# Talon_SDI12.net
KiCad netlist of a schematic drawn in EAGLE
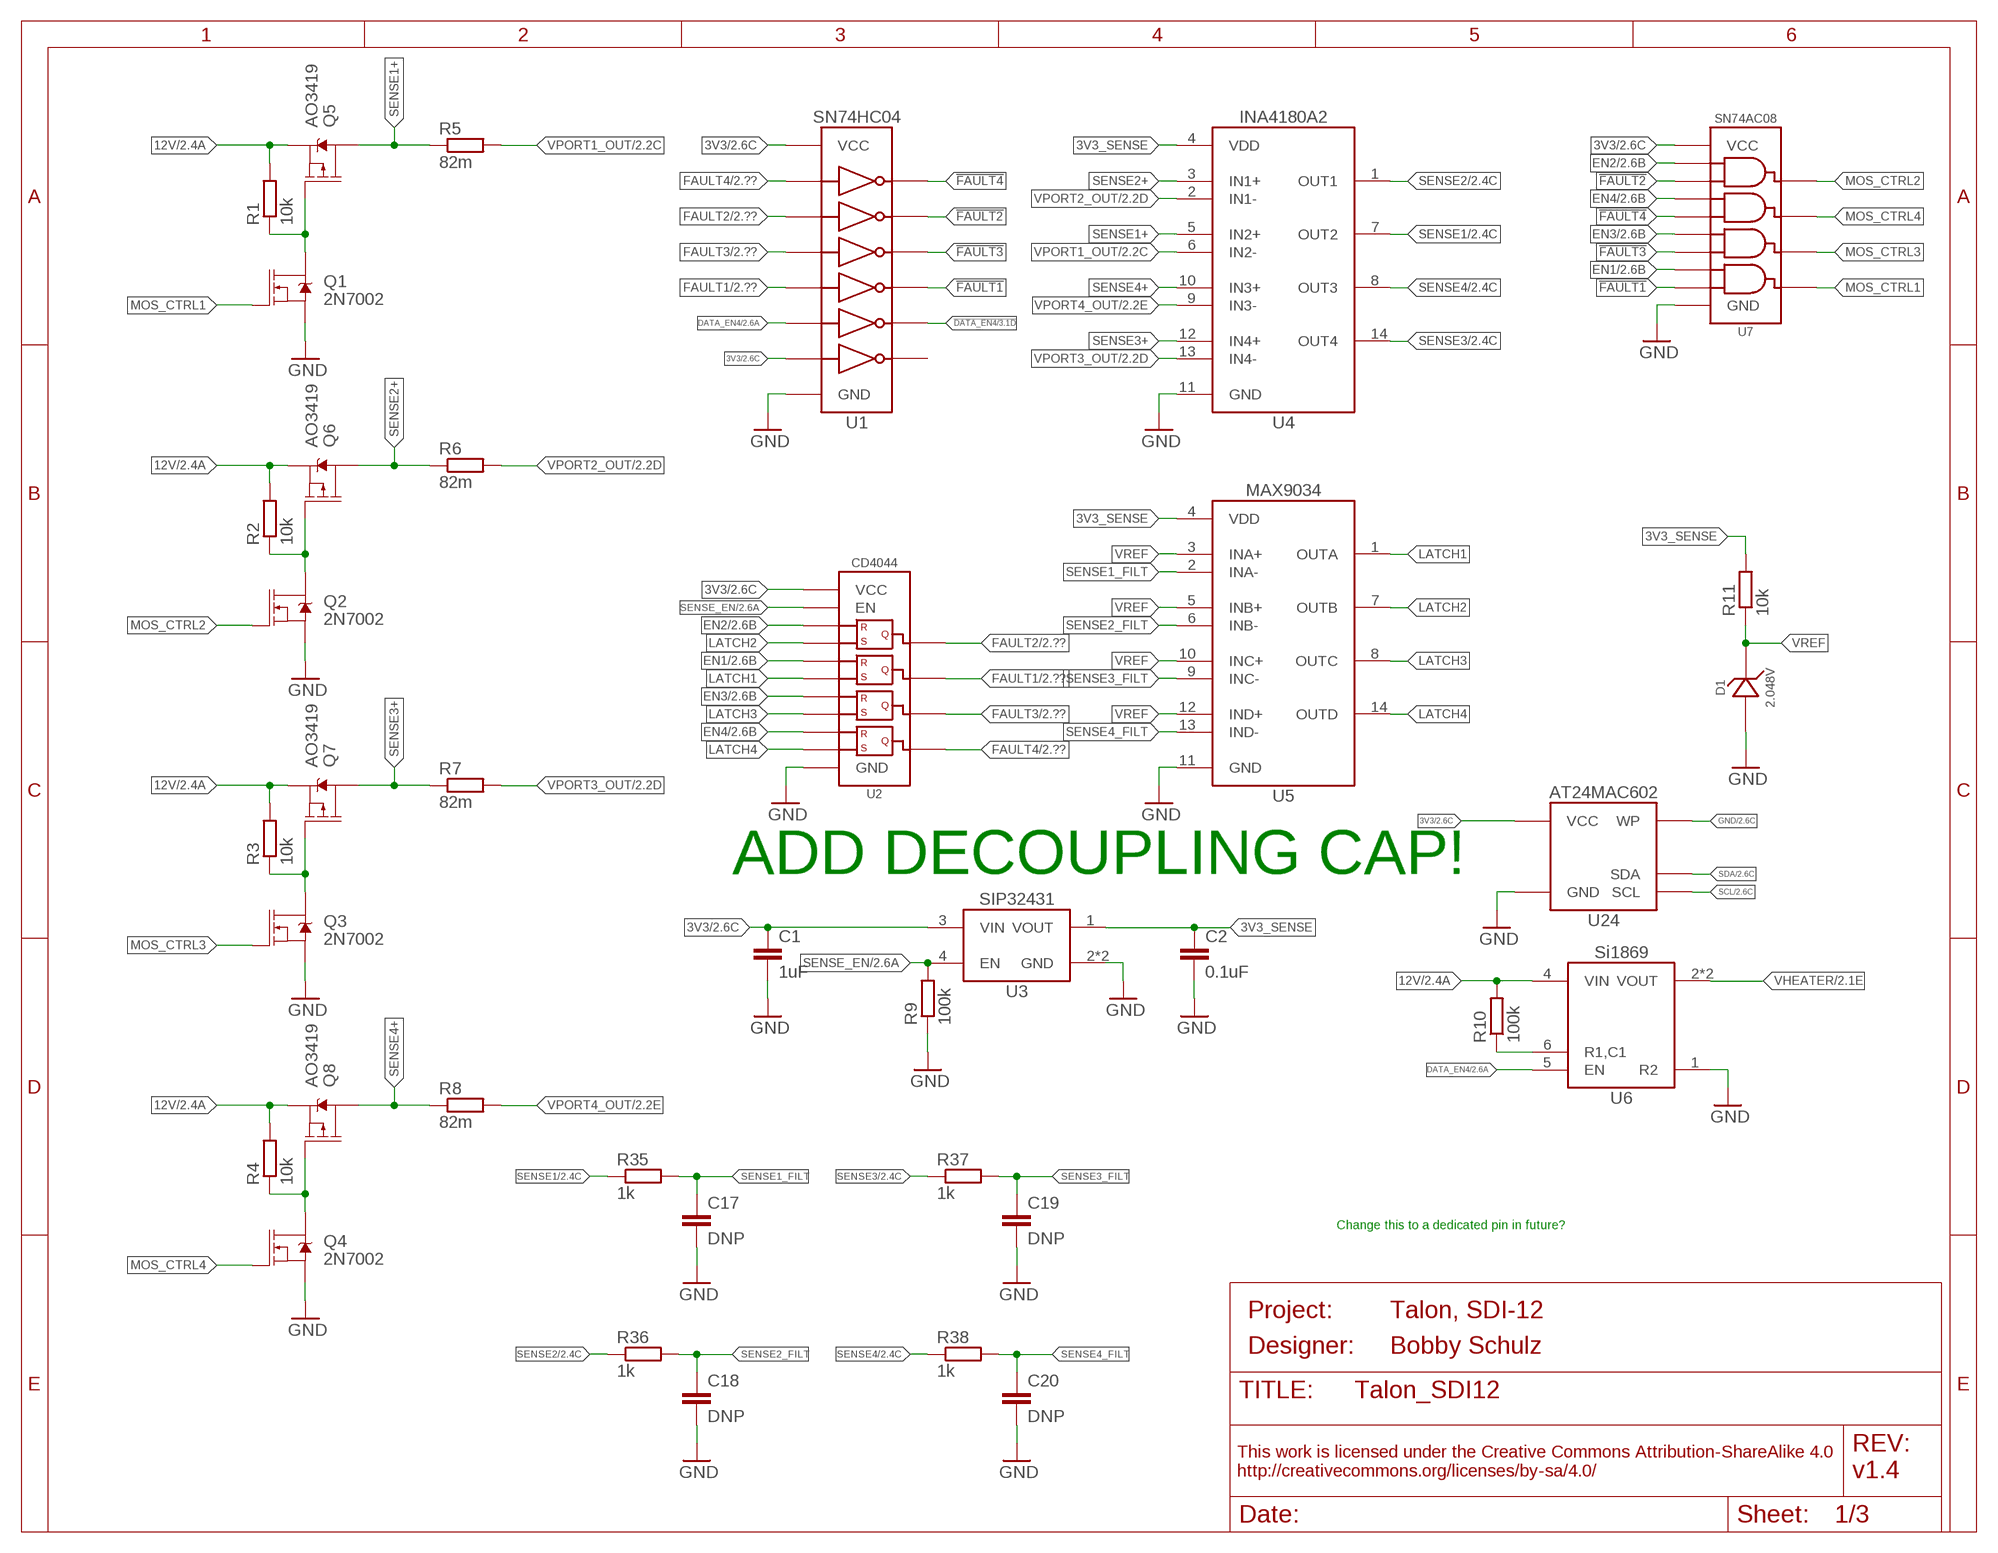
[diagram p0: schematic, sheet 1]
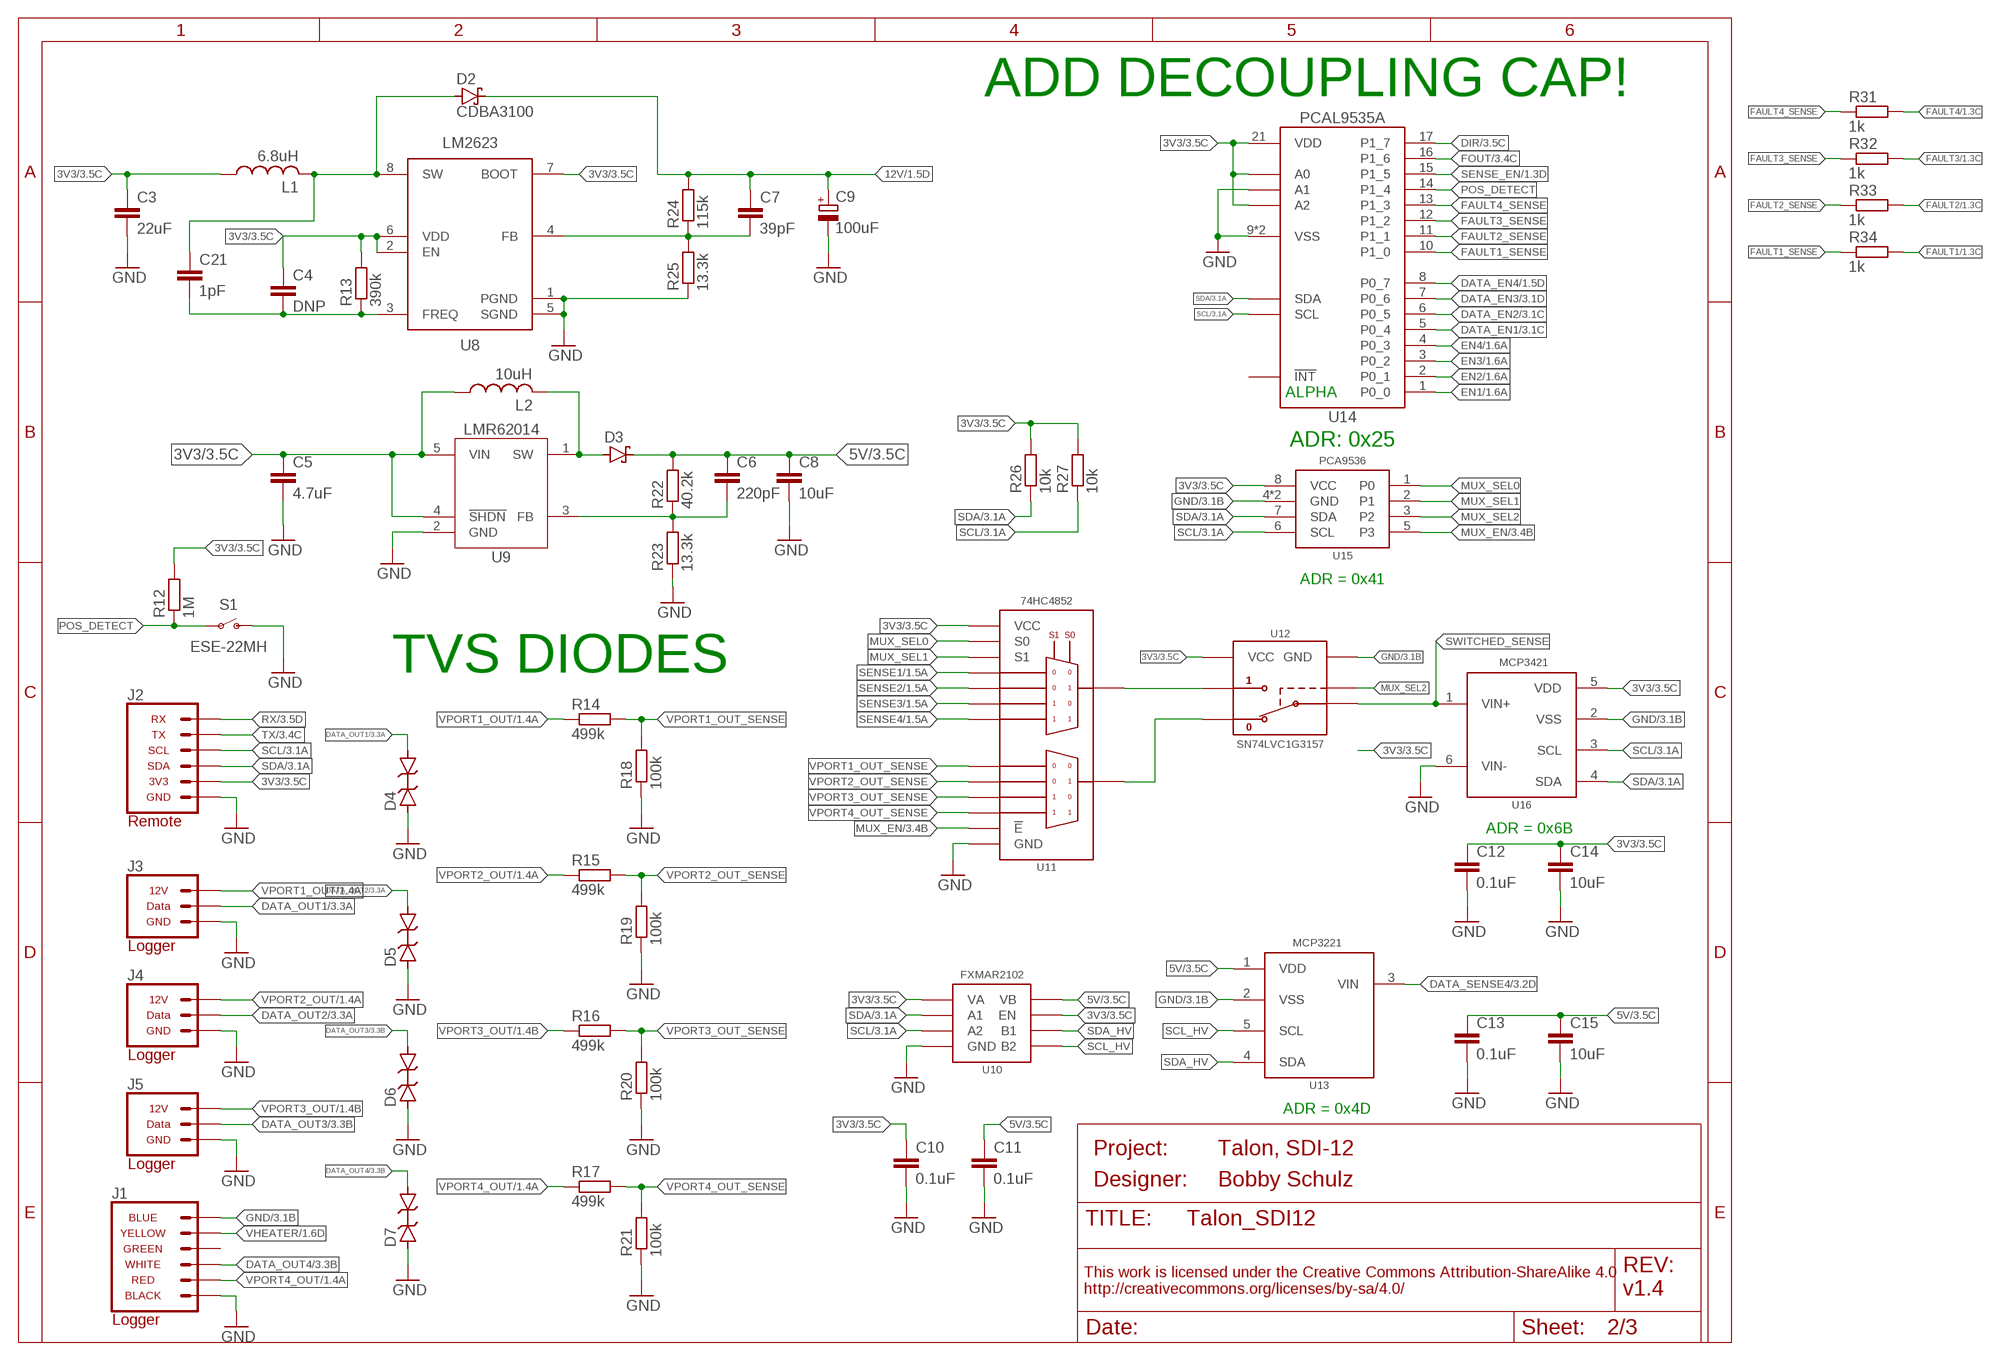
[diagram p1: schematic, sheet 2]
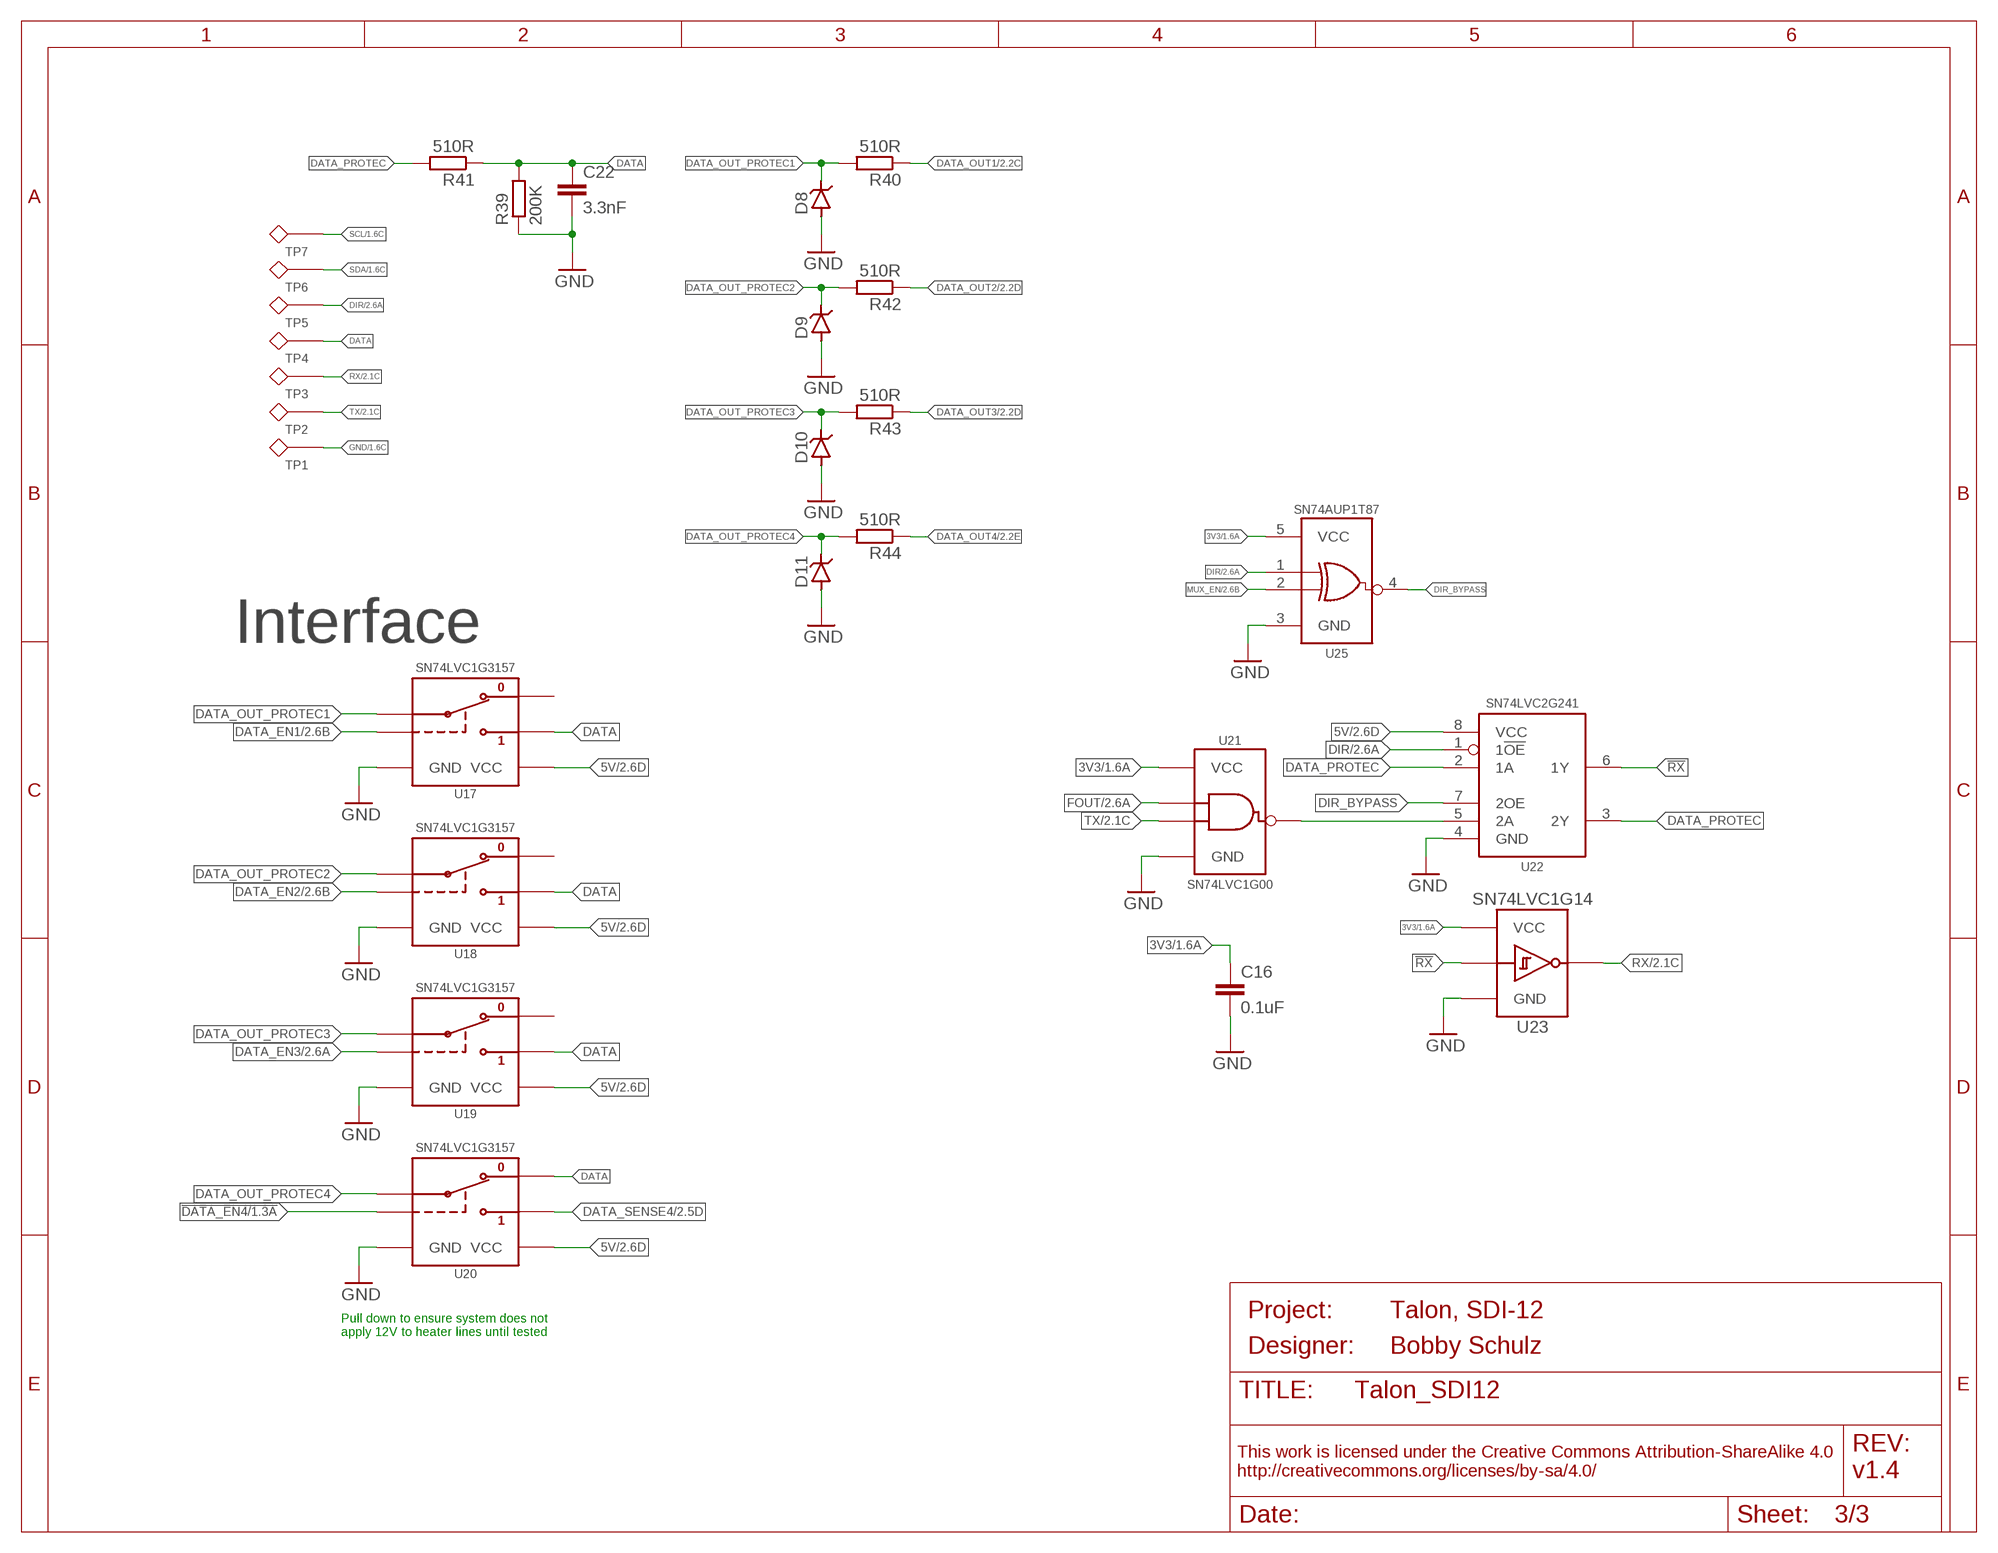
[diagram p2: schematic, sheet 3]

(export (version "E")
  (design (tool "Eeschema 10.0.6"))
  (components
    (comp (ref "C3")
      (value "22uF")
      (footprint "eagle-import:C0805")
      (fields (field (name "MF") "Murata") (field (name "MPN") "GRM219R61C226ME15L"))
      (libsource (lib "eagle-import") (part "C-EUC080522UF"))
    )
    (comp (ref "C4")
      (value "DNP")
      (footprint "eagle-import:C0402")
      (fields
        (field (name "MF") "Murata")
        (field (name "MPN") "GCM155R71C104KA55D")
        (field (name "DIGIKEY") "DNP")
        (field (name "MF_1") "N/A")
        (field (name "MPN_1") "DNP")
      )
      (libsource (lib "eagle-import") (part "C-EUC04020.1UF"))
    )
    (comp (ref "C5")
      (value "4.7uF")
      (footprint "eagle-import:C0805")
      (fields (field (name "MF") "Kemet") (field (name "MPN") "C0805C475K4RACTU"))
      (libsource (lib "eagle-import") (part "C-EUC08054.7UF"))
    )
    (comp (ref "C6")
      (value "220pF")
      (footprint "eagle-import:C0603")
      (fields (field (name "MF") "Kemet") (field (name "MPN") "C0603C221J5GACTU"))
      (libsource (lib "eagle-import") (part "C-EUC0603220PF"))
    )
    (comp (ref "C7")
      (value "39pF")
      (footprint "eagle-import:C0402")
      (fields (field (name "MF") "Kemet") (field (name "MPN") "C0402C390J5GAC7867"))
      (libsource (lib "eagle-import") (part "C-EUC040239PF"))
    )
    (comp (ref "C8")
      (value "10uF")
      (footprint "eagle-import:C0805")
      (fields
        (field (name "MF") "Murata")
        (field (name "MPN") "GRM21BR61C106KE15K")
        (field (name "DIGIKEY") "587-2985-1-ND")
        (field (name "MF_1") "Taiyo Yuden")
        (field (name "MPN_1") "TMK212BBJ106KG-T")
      )
      (libsource (lib "eagle-import") (part "C-EUC080510UF"))
    )
    (comp (ref "C9")
      (value "100uF")
      (footprint "eagle-import:C2917")
      (fields (field (name "MF") "Vishay") (field (name "MPN") "293D107X0016D2TE3"))
      (libsource (lib "eagle-import") (part "CTANT_EU2917"))
    )
    (comp (ref "C10")
      (value "0.1uF")
      (footprint "eagle-import:C0402")
      (fields (field (name "MF") "Murata") (field (name "MPN") "GCM155R71C104KA55D"))
      (libsource (lib "eagle-import") (part "C-EUC04020.1UF"))
    )
    (comp (ref "C11")
      (value "0.1uF")
      (footprint "eagle-import:C0402")
      (fields (field (name "MF") "Murata") (field (name "MPN") "GCM155R71C104KA55D"))
      (libsource (lib "eagle-import") (part "C-EUC04020.1UF"))
    )
    (comp (ref "C12")
      (value "0.1uF")
      (footprint "eagle-import:C0402")
      (fields (field (name "MF") "Murata") (field (name "MPN") "GCM155R71C104KA55D"))
      (libsource (lib "eagle-import") (part "C-EUC04020.1UF"))
    )
    (comp (ref "C13")
      (value "0.1uF")
      (footprint "eagle-import:C0402")
      (fields (field (name "MF") "Murata") (field (name "MPN") "GCM155R71C104KA55D"))
      (libsource (lib "eagle-import") (part "C-EUC04020.1UF"))
    )
    (comp (ref "C14")
      (value "10uF")
      (footprint "eagle-import:C0805")
      (fields (field (name "MF") "Murata") (field (name "MPN") "GRM21BR61C106KE15K"))
      (libsource (lib "eagle-import") (part "C-EUC080510UF"))
    )
    (comp (ref "C15")
      (value "10uF")
      (footprint "eagle-import:C0805")
      (fields (field (name "MF") "Murata") (field (name "MPN") "GRM21BR61C106KE15K"))
      (libsource (lib "eagle-import") (part "C-EUC080510UF"))
    )
    (comp (ref "C21")
      (value "1pF")
      (footprint "eagle-import:C0402")
      (fields (field (name "MF") "Murata") (field (name "MPN") "GJM1555C1H1R0BB01D"))
      (libsource (lib "eagle-import") (part "C-EUC04021PF"))
    )
    (comp (ref "D2")
      (value "CDBA3100")
      (footprint "eagle-import:DO214AC")
      (fields (field (name "MF") "Comchip") (field (name "MPN") "CDBA3100-HF"))
      (libsource (lib "eagle-import") (part "DIODE_SCHOTTKYDO-214AC"))
    )
    (comp (ref "D3")
      (value "DIODE_SCHOTTKYSOD-123")
      (footprint "eagle-import:SOD-123")
      (fields (field (name "MF") "ON Semiconductor") (field (name "MPN") "MBR0520LT1G"))
      (libsource (lib "eagle-import") (part "DIODE_SCHOTTKYSOD-123"))
    )
    (comp (ref "D4")
      (value "12V")
      (footprint "eagle-import:D0402")
      (fields
        (field (name "MF") "Diodes Inc")
        (field (name "MPN") "D5V0L1B2LP4-7B")
        (field (name "DIGIKEY") "D12V0L1B2LP-7BDICT-ND")
        (field (name "MPN_1") "D12V0L1B2LP-7B")
      )
      (libsource (lib "eagle-import") (part "DIODE_ESD_BI_0402_D5V0L1"))
    )
    (comp (ref "D5")
      (value "12V")
      (footprint "eagle-import:D0402")
      (fields
        (field (name "MF") "Diodes Inc")
        (field (name "MPN") "D5V0L1B2LP4-7B")
        (field (name "DIGIKEY") "D12V0L1B2LP-7BDICT-ND")
        (field (name "MPN_1") "D12V0L1B2LP-7B")
      )
      (libsource (lib "eagle-import") (part "DIODE_ESD_BI_0402_D5V0L1"))
    )
    (comp (ref "D6")
      (value "12V")
      (footprint "eagle-import:D0402")
      (fields
        (field (name "MF") "Diodes Inc")
        (field (name "MPN") "D5V0L1B2LP4-7B")
        (field (name "DIGIKEY") "D12V0L1B2LP-7BDICT-ND")
        (field (name "MPN_1") "D12V0L1B2LP-7B")
      )
      (libsource (lib "eagle-import") (part "DIODE_ESD_BI_0402_D5V0L1"))
    )
    (comp (ref "D7")
      (value "12V")
      (footprint "eagle-import:D0402")
      (fields
        (field (name "MF") "Diodes Inc")
        (field (name "MPN") "D5V0L1B2LP4-7B")
        (field (name "DIGIKEY") "D12V0L1B2LP-7BDICT-ND")
        (field (name "MPN_1") "D12V0L1B2LP-7B")
      )
      (libsource (lib "eagle-import") (part "DIODE_ESD_BI_0402_D5V0L1"))
    )
    (comp (ref "J1")
      (value "CONN_APOGEE_LOGGER")
      (footprint "eagle-import:1X06_M8_PHOENIX_1456022_BOARDLOCK")
      (fields
        (field (name "DISP") "Logger")
        (field (name "MF") "Phoenix Contact")
        (field (name "MPN") "1456022")
      )
      (libsource (lib "eagle-import") (part "CONN_APOGEE_LOGGER"))
    )
    (comp (ref "J2")
      (value "CONN_TALON_REMOTE")
      (footprint "eagle-import:1X06_MICROLOCKPLUS")
      (fields (field (name "DISP") "Remote") (field (name "MF") "Molex") (field (name "MPN") "2059570671"))
      (libsource (lib "eagle-import") (part "CONN_TALON_REMOTE"))
    )
    (comp (ref "J3")
      (value "CONN_SDI-12_LOGGERM8_TE_BOARDLOCK")
      (footprint "eagle-import:1X03_M8_TE_T40410_BOARDLOCK")
      (fields
        (field (name "DISP") "Logger")
        (field (name "MF") "TE Connectivity")
        (field (name "MPN") "T4041037031-000")
      )
      (libsource (lib "eagle-import") (part "CONN_SDI-12_LOGGERM8_TE_BOARDLOCK"))
    )
    (comp (ref "J4")
      (value "CONN_SDI-12_LOGGERM8_TE_BOARDLOCK")
      (footprint "eagle-import:1X03_M8_TE_T40410_BOARDLOCK")
      (fields
        (field (name "DISP") "Logger")
        (field (name "MF") "TE Connectivity")
        (field (name "MPN") "T4041037031-000")
      )
      (libsource (lib "eagle-import") (part "CONN_SDI-12_LOGGERM8_TE_BOARDLOCK"))
    )
    (comp (ref "J5")
      (value "CONN_SDI-12_LOGGERM8_TE_BOARDLOCK")
      (footprint "eagle-import:1X03_M8_TE_T40410_BOARDLOCK")
      (fields
        (field (name "DISP") "Logger")
        (field (name "MF") "TE Connectivity")
        (field (name "MPN") "T4041037031-000")
      )
      (libsource (lib "eagle-import") (part "CONN_SDI-12_LOGGERM8_TE_BOARDLOCK"))
    )
    (comp (ref "L1")
      (value "6.8uH")
      (footprint "eagle-import:WE-MAIA(4.1X4.1)")
      (fields (field (name "MF") "Wurth") (field (name "MPN") "78438357068"))
      (libsource (lib "eagle-import") (part "INDUCTOR_MAIA_4.1X4.1"))
    )
    (comp (ref "L2")
      (value "10uH")
      (footprint "eagle-import:1008")
      (fields (field (name "MF") "Wurth") (field (name "MPN") "74438323100"))
      (libsource (lib "eagle-import") (part "INDUCTOR_1008"))
    )
    (comp (ref "R12")
      (value "1M")
      (footprint "eagle-import:R0402")
      (fields (field (name "MF") "Yageo") (field (name "MPN") "RC0402FR-071ML"))
      (libsource (lib "eagle-import") (part "R-EU_R04021M"))
    )
    (comp (ref "R13")
      (value "390k")
      (footprint "eagle-import:R0603")
      (fields (field (name "MF") "Yageo") (field (name "MPN") "RC0603FR-07390KL"))
      (libsource (lib "eagle-import") (part "R-EU_R0603390K"))
    )
    (comp (ref "R14")
      (value "499k")
      (footprint "eagle-import:R0603")
      (fields (field (name "MF") "Yageo") (field (name "MPN") "RC0603FR-07499KL"))
      (libsource (lib "eagle-import") (part "R-EU_R0603499K"))
    )
    (comp (ref "R15")
      (value "499k")
      (footprint "eagle-import:R0603")
      (fields (field (name "MF") "Yageo") (field (name "MPN") "RC0603FR-07499KL"))
      (libsource (lib "eagle-import") (part "R-EU_R0603499K"))
    )
    (comp (ref "R16")
      (value "499k")
      (footprint "eagle-import:R0603")
      (fields (field (name "MF") "Yageo") (field (name "MPN") "RC0603FR-07499KL"))
      (libsource (lib "eagle-import") (part "R-EU_R0603499K"))
    )
    (comp (ref "R17")
      (value "499k")
      (footprint "eagle-import:R0603")
      (fields (field (name "MF") "Yageo") (field (name "MPN") "RC0603FR-07499KL"))
      (libsource (lib "eagle-import") (part "R-EU_R0603499K"))
    )
    (comp (ref "R18")
      (value "100k")
      (footprint "eagle-import:R0402")
      (fields (field (name "MF") "Yageo") (field (name "MPN") "RC0402FR-07100KL"))
      (libsource (lib "eagle-import") (part "R-EU_R0402100K"))
    )
    (comp (ref "R19")
      (value "100k")
      (footprint "eagle-import:R0402")
      (fields (field (name "MF") "Yageo") (field (name "MPN") "RC0402FR-07100KL"))
      (libsource (lib "eagle-import") (part "R-EU_R0402100K"))
    )
    (comp (ref "R20")
      (value "100k")
      (footprint "eagle-import:R0402")
      (fields (field (name "MF") "Yageo") (field (name "MPN") "RC0402FR-07100KL"))
      (libsource (lib "eagle-import") (part "R-EU_R0402100K"))
    )
    (comp (ref "R21")
      (value "100k")
      (footprint "eagle-import:R0402")
      (fields (field (name "MF") "Yageo") (field (name "MPN") "RC0402FR-07100KL"))
      (libsource (lib "eagle-import") (part "R-EU_R0402100K"))
    )
    (comp (ref "R22")
      (value "40.2k")
      (footprint "eagle-import:R0603")
      (fields (field (name "MF") "Stackpole") (field (name "MPN") "RMCF0603FT40K2"))
      (libsource (lib "eagle-import") (part "R-EU_R060340.2K"))
    )
    (comp (ref "R23")
      (value "13.3k")
      (footprint "eagle-import:R0603")
      (fields (field (name "MF") "Yageo") (field (name "MPN") "RC0603FR-0713K3L"))
      (libsource (lib "eagle-import") (part "R-EU_R060313.3K"))
    )
    (comp (ref "R24")
      (value "115k")
      (footprint "eagle-import:R0603")
      (fields (field (name "MF") "Yageo") (field (name "MPN") "RC0603FR-07115KL"))
      (libsource (lib "eagle-import") (part "R-EU_R0603115K"))
    )
    (comp (ref "R25")
      (value "13.3k")
      (footprint "eagle-import:R0603")
      (fields (field (name "MF") "Yageo") (field (name "MPN") "RC0603FR-0713K3L"))
      (libsource (lib "eagle-import") (part "R-EU_R060313.3K"))
    )
    (comp (ref "R26")
      (value "10k")
      (footprint "eagle-import:R0402")
      (fields (field (name "MF") "Yageo") (field (name "MPN") "RC0402FR-0710KL"))
      (libsource (lib "eagle-import") (part "R-EU_R040210K"))
    )
    (comp (ref "R27")
      (value "10k")
      (footprint "eagle-import:R0402")
      (fields (field (name "MF") "Yageo") (field (name "MPN") "RC0402FR-0710KL"))
      (libsource (lib "eagle-import") (part "R-EU_R040210K"))
    )
    (comp (ref "R31")
      (value "1k")
      (footprint "eagle-import:R0402")
      (fields (field (name "MF") "Yageo") (field (name "MPN") "RC0402FR-071KL"))
      (libsource (lib "eagle-import") (part "R-EU_R04021K"))
    )
    (comp (ref "R32")
      (value "1k")
      (footprint "eagle-import:R0402")
      (fields (field (name "MF") "Yageo") (field (name "MPN") "RC0402FR-071KL"))
      (libsource (lib "eagle-import") (part "R-EU_R04021K"))
    )
    (comp (ref "R33")
      (value "1k")
      (footprint "eagle-import:R0402")
      (fields (field (name "MF") "Yageo") (field (name "MPN") "RC0402FR-071KL"))
      (libsource (lib "eagle-import") (part "R-EU_R04021K"))
    )
    (comp (ref "R34")
      (value "1k")
      (footprint "eagle-import:R0402")
      (fields (field (name "MF") "Yageo") (field (name "MPN") "RC0402FR-071KL"))
      (libsource (lib "eagle-import") (part "R-EU_R04021K"))
    )
    (comp (ref "S1")
      (value "ESE-22MH")
      (footprint "eagle-import:ESE-22MH")
      (fields (field (name "MF") "Panasonic") (field (name "MPN") "ESE-22MH24"))
      (libsource (lib "eagle-import") (part "SPSTESE-22MH"))
    )
    (comp (ref "U8")
      (value "LM2621")
      (footprint "eagle-import:DGK_S-PDSO-G8")
      (fields
        (field (name "DISP") "LM2621")
        (field (name "MF") "TI")
        (field (name "MPN") "LM2621MMX/NOPB")
        (field (name "DIGIKEY") "LM2623AMM/NOPBCT-ND")
        (field (name "DISP_1") "LM2623")
        (field (name "MPN_1") "LM2623AMM/NOPB")
      )
      (libsource (lib "eagle-import") (part "LM2621"))
    )
    (comp (ref "U9")
      (value "LMR62014SOT23")
      (footprint "eagle-import:DBV0005A")
      (fields
        (field (name "DISP") "LMR62014")
        (field (name "MF") "TI")
        (field (name "MPN") "LMR62014XMF/NOPB")
      )
      (libsource (lib "eagle-import") (part "LMR62014SOT23"))
    )
    (comp (ref "U10")
      (value "FXMAR2102UMLP")
      (footprint "eagle-import:UQFN-8_1.4X1.2")
      (fields
        (field (name "DISP") "FXMAR2102")
        (field (name "MF") "OnSemi")
        (field (name "MPN") "FXMAR2102UMX-F106")
      )
      (libsource (lib "eagle-import") (part "FXMAR2102UMLP"))
    )
    (comp (ref "U11")
      (value "74HC4852")
      (footprint "eagle-import:VQFN-16")
      (fields
        (field (name "DISP") "74HC4852")
        (field (name "MF") "Nexperia")
        (field (name "MPN") "74HC4852BQ-Q100,11")
      )
      (libsource (lib "eagle-import") (part "74HC4852"))
    )
    (comp (ref "U12")
      (value "SN74LVC1G3157SC70")
      (footprint "eagle-import:DCK_R-PDSO-G6")
      (fields
        (field (name "DISP") "SN74LVC1G3157")
        (field (name "MF") "TI")
        (field (name "MPN") "SN74LVC1G3157DCKR")
      )
      (libsource (lib "eagle-import") (part "SN74LVC1G3157SC70"))
    )
    (comp (ref "U13")
      (value "MCP3221")
      (footprint "eagle-import:SOT23-5")
      (fields (field (name "DISP") "MCP3221") (field (name "MF") "TI") (field (name "MPN") "MCP3221A5T-I/OT"))
      (libsource (lib "eagle-import") (part "MCP3221"))
    )
    (comp (ref "U14")
      (value "PCAL9535AQFN")
      (footprint "eagle-import:QFN24")
      (fields
        (field (name "DISP") "PCAL9535A")
        (field (name "MF") "NXP")
        (field (name "MPN") "PCAL9535AHF,128")
      )
      (libsource (lib "eagle-import") (part "PCAL955AQFN3"))
    )
    (comp (ref "U15")
      (value "PCA9536DFN")
      (footprint "eagle-import:DFN_8_3X3")
      (fields (field (name "MF") "NXP") (field (name "MPN") "PCA9536TK,118"))
      (libsource (lib "eagle-import") (part "PCA9536DFN"))
    )
    (comp (ref "U16")
      (value "MCP3421A3")
      (footprint "eagle-import:SOT23-6L")
      (fields
        (field (name "DISP") "MCP3421")
        (field (name "MF") "Microchip")
        (field (name "MPN") "MCP3421A3T-E/CH")
      )
      (libsource (lib "eagle-import") (part "MCP3421A3"))
    )
    (comp (ref "C1")
      (value "1uF")
      (footprint "eagle-import:C0603")
      (fields (field (name "MF") "Yaiyo Yuden") (field (name "MPN") "TMK107B7105KA-T"))
      (libsource (lib "eagle-import") (part "C-EUC06031UF"))
    )
    (comp (ref "C2")
      (value "0.1uF")
      (footprint "eagle-import:C0402")
      (fields (field (name "MF") "Murata") (field (name "MPN") "GCM155R71C104KA55D"))
      (libsource (lib "eagle-import") (part "C-EUC04020.1UF"))
    )
    (comp (ref "C17")
      (value "DNP")
      (footprint "eagle-import:C0402")
      (fields
        (field (name "MF") "Murata")
        (field (name "MPN") "GCM155R71C104KA55D")
        (field (name "DIGIKEY") "DNP")
        (field (name "MF_1") "N/A")
        (field (name "MPN_1") "DNP")
      )
      (libsource (lib "eagle-import") (part "C-EUC04020.1UF"))
    )
    (comp (ref "C18")
      (value "DNP")
      (footprint "eagle-import:C0402")
      (fields
        (field (name "MF") "Murata")
        (field (name "MPN") "GCM155R71C104KA55D")
        (field (name "DIGIKEY") "DNP")
        (field (name "MF_1") "N/A")
        (field (name "MPN_1") "DNP")
      )
      (libsource (lib "eagle-import") (part "C-EUC04020.1UF"))
    )
    (comp (ref "C19")
      (value "DNP")
      (footprint "eagle-import:C0402")
      (fields
        (field (name "MF") "Murata")
        (field (name "MPN") "GCM155R71C104KA55D")
        (field (name "DIGIKEY") "DNP")
        (field (name "MF_1") "N/A")
        (field (name "MPN_1") "DNP")
      )
      (libsource (lib "eagle-import") (part "C-EUC04020.1UF"))
    )
    (comp (ref "C20")
      (value "DNP")
      (footprint "eagle-import:C0402")
      (fields
        (field (name "MF") "Murata")
        (field (name "MPN") "GCM155R71C104KA55D")
        (field (name "DIGIKEY") "DNP")
        (field (name "MF_1") "N/A")
        (field (name "MPN_1") "DNP")
      )
      (libsource (lib "eagle-import") (part "C-EUC04020.1UF"))
    )
    (comp (ref "D1")
      (value "2.048V")
      (footprint "eagle-import:SOT23-3")
      (fields (field (name "MF") "TI") (field (name "MPN") "LM4040CIM3-2.0/NOPB"))
      (libsource (lib "eagle-import") (part "LM40402.048"))
    )
    (comp (ref "Q1")
      (value "2N7002")
      (footprint "eagle-import:SOT23-3")
      (fields (field (name "MF") "Nexperia") (field (name "MPN") "2N7002P,215"))
      (libsource (lib "eagle-import") (part "MOSFET-NCH-2N7002P"))
    )
    (comp (ref "Q2")
      (value "2N7002")
      (footprint "eagle-import:SOT23-3")
      (fields (field (name "MF") "Nexperia") (field (name "MPN") "2N7002P,215"))
      (libsource (lib "eagle-import") (part "MOSFET-NCH-2N7002P"))
    )
    (comp (ref "Q3")
      (value "2N7002")
      (footprint "eagle-import:SOT23-3")
      (fields (field (name "MF") "Nexperia") (field (name "MPN") "2N7002P,215"))
      (libsource (lib "eagle-import") (part "MOSFET-NCH-2N7002P"))
    )
    (comp (ref "Q4")
      (value "2N7002")
      (footprint "eagle-import:SOT23-3")
      (fields (field (name "MF") "Nexperia") (field (name "MPN") "2N7002P,215"))
      (libsource (lib "eagle-import") (part "MOSFET-NCH-2N7002P"))
    )
    (comp (ref "Q5")
      (value "AO3419")
      (footprint "eagle-import:SOT23-3")
      (fields (field (name "MF") "Alpha and Omega"))
      (libsource (lib "eagle-import") (part "MOSFET-PCH-AO3419"))
    )
    (comp (ref "Q6")
      (value "AO3419")
      (footprint "eagle-import:SOT23-3")
      (fields (field (name "MF") "Alpha and Omega"))
      (libsource (lib "eagle-import") (part "MOSFET-PCH-AO3419"))
    )
    (comp (ref "Q7")
      (value "AO3419")
      (footprint "eagle-import:SOT23-3")
      (fields (field (name "MF") "Alpha and Omega"))
      (libsource (lib "eagle-import") (part "MOSFET-PCH-AO3419"))
    )
    (comp (ref "Q8")
      (value "AO3419")
      (footprint "eagle-import:SOT23-3")
      (fields (field (name "MF") "Alpha and Omega"))
      (libsource (lib "eagle-import") (part "MOSFET-PCH-AO3419"))
    )
    (comp (ref "R1")
      (value "10k")
      (footprint "eagle-import:R0402")
      (fields (field (name "MF") "Yageo") (field (name "MPN") "RC0402FR-0710KL"))
      (libsource (lib "eagle-import") (part "R-EU_R040210K"))
    )
    (comp (ref "R2")
      (value "10k")
      (footprint "eagle-import:R0402")
      (fields (field (name "MF") "Yageo") (field (name "MPN") "RC0402FR-0710KL"))
      (libsource (lib "eagle-import") (part "R-EU_R040210K"))
    )
    (comp (ref "R3")
      (value "10k")
      (footprint "eagle-import:R0402")
      (fields (field (name "MF") "Yageo") (field (name "MPN") "RC0402FR-0710KL"))
      (libsource (lib "eagle-import") (part "R-EU_R040210K"))
    )
    (comp (ref "R4")
      (value "10k")
      (footprint "eagle-import:R0402")
      (fields (field (name "MF") "Yageo") (field (name "MPN") "RC0402FR-0710KL"))
      (libsource (lib "eagle-import") (part "R-EU_R040210K"))
    )
    (comp (ref "R5")
      (value "82m")
      (footprint "eagle-import:R0603")
      (fields (field (name "MF") "Susumu") (field (name "MPN") "RL0816T-R082-F"))
      (libsource (lib "eagle-import") (part "R-EU_R06030.082"))
    )
    (comp (ref "R6")
      (value "82m")
      (footprint "eagle-import:R0603")
      (fields (field (name "MF") "Susumu") (field (name "MPN") "RL0816T-R082-F"))
      (libsource (lib "eagle-import") (part "R-EU_R06030.082"))
    )
    (comp (ref "R7")
      (value "82m")
      (footprint "eagle-import:R0603")
      (fields (field (name "MF") "Susumu") (field (name "MPN") "RL0816T-R082-F"))
      (libsource (lib "eagle-import") (part "R-EU_R06030.082"))
    )
    (comp (ref "R8")
      (value "82m")
      (footprint "eagle-import:R0603")
      (fields (field (name "MF") "Susumu") (field (name "MPN") "RL0816T-R082-F"))
      (libsource (lib "eagle-import") (part "R-EU_R06030.082"))
    )
    (comp (ref "R9")
      (value "100k")
      (footprint "eagle-import:R0402")
      (fields (field (name "MF") "Yageo") (field (name "MPN") "RC0402FR-07100KL"))
      (libsource (lib "eagle-import") (part "R-EU_R0402100K"))
    )
    (comp (ref "R10")
      (value "100k")
      (footprint "eagle-import:R0402")
      (fields (field (name "MF") "Yageo") (field (name "MPN") "RC0402FR-07100KL"))
      (libsource (lib "eagle-import") (part "R-EU_R0402100K"))
    )
    (comp (ref "R11")
      (value "10k")
      (footprint "eagle-import:R0402")
      (fields (field (name "MF") "Yageo") (field (name "MPN") "RC0402FR-0710KL"))
      (libsource (lib "eagle-import") (part "R-EU_R040210K"))
    )
    (comp (ref "R35")
      (value "1k")
      (footprint "eagle-import:R0402")
      (fields (field (name "MF") "Yageo") (field (name "MPN") "RC0402FR-071KL"))
      (libsource (lib "eagle-import") (part "R-EU_R04021K"))
    )
    (comp (ref "R36")
      (value "1k")
      (footprint "eagle-import:R0402")
      (fields (field (name "MF") "Yageo") (field (name "MPN") "RC0402FR-071KL"))
      (libsource (lib "eagle-import") (part "R-EU_R04021K"))
    )
    (comp (ref "R37")
      (value "1k")
      (footprint "eagle-import:R0402")
      (fields (field (name "MF") "Yageo") (field (name "MPN") "RC0402FR-071KL"))
      (libsource (lib "eagle-import") (part "R-EU_R04021K"))
    )
    (comp (ref "R38")
      (value "1k")
      (footprint "eagle-import:R0402")
      (fields (field (name "MF") "Yageo") (field (name "MPN") "RC0402FR-071KL"))
      (libsource (lib "eagle-import") (part "R-EU_R04021K"))
    )
    (comp (ref "U1")
      (value "SN74HC04")
      (footprint "eagle-import:TSSOP14")
      (fields (field (name "MF") "TI") (field (name "MPN") "SN74HC04PWR"))
      (libsource (lib "eagle-import") (part "SN74HC04"))
    )
    (comp (ref "U2")
      (value "CD4044")
      (footprint "eagle-import:TSSOP16")
      (fields (field (name "DISP") "CD4044") (field (name "MF") "TI") (field (name "MPN") "CD4044BPWR"))
      (libsource (lib "eagle-import") (part "CD4044"))
    )
    (comp (ref "U3")
      (value "SIP32431TDFN")
      (footprint "eagle-import:TDFN_4")
      (fields
        (field (name "DISP") "SIP32431")
        (field (name "MF") "Vishay")
        (field (name "MPN") "SIP32431DNP3-T1GE4")
      )
      (libsource (lib "eagle-import") (part "SIP3243TDFN1"))
    )
    (comp (ref "U4")
      (value "INA4180A2")
      (footprint "eagle-import:TSSOP14")
      (fields (field (name "DISP") "INA4180A2") (field (name "MF") "TI") (field (name "MPN") "INA4180A2IPWR"))
      (libsource (lib "eagle-import") (part "INA4180A2"))
    )
    (comp (ref "U5")
      (value "MAX9034TSSOP")
      (footprint "eagle-import:TSSOP14")
      (fields (field (name "DISP") "MAX9034") (field (name "MF") "Maxim") (field (name "MPN") "MAX9034AUD+T"))
      (libsource (lib "eagle-import") (part "MAX9034TSSOP"))
    )
    (comp (ref "U6")
      (value "SI1869")
      (footprint "eagle-import:SC-70_6")
      (fields
        (field (name "DISP") "Si1869")
        (field (name "MF") "Vishay")
        (field (name "MPN") "SI1869DH-T1-E3")
      )
      (libsource (lib "eagle-import") (part "SI1869"))
    )
    (comp (ref "U7")
      (value "SN74AC08")
      (footprint "eagle-import:TSSOP14")
      (fields (field (name "MF") "TI") (field (name "MPN") "SN74AC08PWR"))
      (libsource (lib "eagle-import") (part "SN74AC08"))
    )
    (comp (ref "U24")
      (value "AT24MAC602SOT23")
      (footprint "eagle-import:SOT23-5")
      (fields
        (field (name "DISP") "AT24MAC602")
        (field (name "MF") "Microchip")
        (field (name "MPN") "AT24MAC602-STUM-T")
      )
      (libsource (lib "eagle-import") (part "AT24MAC02SOT236"))
    )
    (comp (ref "C16")
      (value "0.1uF")
      (footprint "eagle-import:C0402")
      (fields (field (name "MF") "Murata") (field (name "MPN") "GCM155R71C104KA55D"))
      (libsource (lib "eagle-import") (part "C-EUC04020.1UF"))
    )
    (comp (ref "C22")
      (value "3.3nF")
      (footprint "eagle-import:C0402")
      (fields (field (name "MF") "Yageo") (field (name "MPN") "CC0402KRX7R9BB332"))
      (libsource (lib "eagle-import") (part "C-EUC04023.3NF"))
    )
    (comp (ref "D8")
      (value "DIODE_ZENERSOD-323")
      (footprint "eagle-import:SOD323-R")
      (fields (field (name "MF") "Vishay") (field (name "MPN") "BZX384B5V1-HE3-08"))
      (libsource (lib "eagle-import") (part "DIODE_ZENERSOD-323"))
    )
    (comp (ref "D9")
      (value "DIODE_ZENERSOD-323")
      (footprint "eagle-import:SOD323-R")
      (fields (field (name "MF") "Vishay") (field (name "MPN") "BZX384B5V1-HE3-08"))
      (libsource (lib "eagle-import") (part "DIODE_ZENERSOD-323"))
    )
    (comp (ref "D10")
      (value "DIODE_ZENERSOD-323")
      (footprint "eagle-import:SOD323-R")
      (fields (field (name "MF") "Vishay") (field (name "MPN") "BZX384B5V1-HE3-08"))
      (libsource (lib "eagle-import") (part "DIODE_ZENERSOD-323"))
    )
    (comp (ref "D11")
      (value "DIODE_ZENERSOD-323")
      (footprint "eagle-import:SOD323-R")
      (fields (field (name "MF") "Vishay") (field (name "MPN") "BZX384B5V1-HE3-08"))
      (libsource (lib "eagle-import") (part "DIODE_ZENERSOD-323"))
    )
    (comp (ref "R39")
      (value "200K")
      (footprint "eagle-import:R0402")
      (fields
        (field (name "MF") "Yageo")
        (field (name "MPN") "RC0402FR-07200KL")
        (field (name "VALUE_PART") "200k")
      )
      (libsource (lib "eagle-import") (part "R-EU_R0402200K"))
    )
    (comp (ref "R40")
      (value "510R")
      (footprint "eagle-import:R0402")
      (fields
        (field (name "MF") "Yageo")
        (field (name "MPN") "RC0402FR-07510RL")
        (field (name "VALUE_PART") "510")
      )
      (libsource (lib "eagle-import") (part "R-EU_R0402510"))
    )
    (comp (ref "R41")
      (value "510R")
      (footprint "eagle-import:R0402")
      (fields
        (field (name "MF") "Yageo")
        (field (name "MPN") "RC0402FR-07510RL")
        (field (name "VALUE_PART") "510")
      )
      (libsource (lib "eagle-import") (part "R-EU_R0402510"))
    )
    (comp (ref "R42")
      (value "510R")
      (footprint "eagle-import:R0402")
      (fields
        (field (name "MF") "Yageo")
        (field (name "MPN") "RC0402FR-07510RL")
        (field (name "VALUE_PART") "510")
      )
      (libsource (lib "eagle-import") (part "R-EU_R0402510"))
    )
    (comp (ref "R43")
      (value "510R")
      (footprint "eagle-import:R0402")
      (fields
        (field (name "MF") "Yageo")
        (field (name "MPN") "RC0402FR-07510RL")
        (field (name "VALUE_PART") "510")
      )
      (libsource (lib "eagle-import") (part "R-EU_R0402510"))
    )
    (comp (ref "R44")
      (value "510R")
      (footprint "eagle-import:R0402")
      (fields
        (field (name "MF") "Yageo")
        (field (name "MPN") "RC0402FR-07510RL")
        (field (name "VALUE_PART") "510")
      )
      (libsource (lib "eagle-import") (part "R-EU_R0402510"))
    )
    (comp (ref "TP1")
      (value "TESTPOINTRCU")
      (footprint "eagle-import:TESTPOINT_0603")
      (fields (field (name "MF") "TE Connectivity") (field (name "MPN") "RCU-0C"))
      (libsource (lib "eagle-import") (part "TESTPOINTRCU"))
    )
    (comp (ref "TP2")
      (value "TESTPOINTRCU")
      (footprint "eagle-import:TESTPOINT_0603")
      (fields (field (name "MF") "TE Connectivity") (field (name "MPN") "RCU-0C"))
      (libsource (lib "eagle-import") (part "TESTPOINTRCU"))
    )
    (comp (ref "TP3")
      (value "TESTPOINTRCU")
      (footprint "eagle-import:TESTPOINT_0603")
      (fields (field (name "MF") "TE Connectivity") (field (name "MPN") "RCU-0C"))
      (libsource (lib "eagle-import") (part "TESTPOINTRCU"))
    )
    (comp (ref "TP4")
      (value "TESTPOINTRCU")
      (footprint "eagle-import:TESTPOINT_0603")
      (fields (field (name "MF") "TE Connectivity") (field (name "MPN") "RCU-0C"))
      (libsource (lib "eagle-import") (part "TESTPOINTRCU"))
    )
    (comp (ref "TP5")
      (value "TESTPOINTRCU")
      (footprint "eagle-import:TESTPOINT_0603")
      (fields (field (name "MF") "TE Connectivity") (field (name "MPN") "RCU-0C"))
      (libsource (lib "eagle-import") (part "TESTPOINTRCU"))
    )
    (comp (ref "TP6")
      (value "TESTPOINTRCU")
      (footprint "eagle-import:TESTPOINT_0603")
      (fields (field (name "MF") "TE Connectivity") (field (name "MPN") "RCU-0C"))
      (libsource (lib "eagle-import") (part "TESTPOINTRCU"))
    )
    (comp (ref "TP7")
      (value "TESTPOINTRCU")
      (footprint "eagle-import:TESTPOINT_0603")
      (fields (field (name "MF") "TE Connectivity") (field (name "MPN") "RCU-0C"))
      (libsource (lib "eagle-import") (part "TESTPOINTRCU"))
    )
    (comp (ref "U17")
      (value "SN74LVC1G3157SC70")
      (footprint "eagle-import:DCK_R-PDSO-G6")
      (fields
        (field (name "DISP") "SN74LVC1G3157")
        (field (name "MF") "TI")
        (field (name "MPN") "SN74LVC1G3157DCKR")
      )
      (libsource (lib "eagle-import") (part "SN74LVC1G3157SC70"))
    )
    (comp (ref "U18")
      (value "SN74LVC1G3157SC70")
      (footprint "eagle-import:DCK_R-PDSO-G6")
      (fields
        (field (name "DISP") "SN74LVC1G3157")
        (field (name "MF") "TI")
        (field (name "MPN") "SN74LVC1G3157DCKR")
      )
      (libsource (lib "eagle-import") (part "SN74LVC1G3157SC70"))
    )
    (comp (ref "U19")
      (value "SN74LVC1G3157SC70")
      (footprint "eagle-import:DCK_R-PDSO-G6")
      (fields
        (field (name "DISP") "SN74LVC1G3157")
        (field (name "MF") "TI")
        (field (name "MPN") "SN74LVC1G3157DCKR")
      )
      (libsource (lib "eagle-import") (part "SN74LVC1G3157SC70"))
    )
    (comp (ref "U20")
      (value "SN74LVC1G3157SC70")
      (footprint "eagle-import:DCK_R-PDSO-G6")
      (fields
        (field (name "DISP") "SN74LVC1G3157")
        (field (name "MF") "TI")
        (field (name "MPN") "SN74LVC1G3157DCKR")
      )
      (libsource (lib "eagle-import") (part "SN74LVC1G3157SC70"))
    )
    (comp (ref "U21")
      (value "SN74LVC1G00SC70")
      (footprint "eagle-import:DCK_R-PDSO-G5")
      (fields (field (name "DISP") "SN74LVC1G00") (field (name "MPN") "SN74LVC1G00DCKR"))
      (libsource (lib "eagle-import") (part "SN74LVC1G00SC70"))
    )
    (comp (ref "U22")
      (value "SN74LVC2G241DCU")
      (footprint "eagle-import:DCU_(R-PDSO-G8)")
      (fields (field (name "MF") "TI") (field (name "MPN") "SN74LVC2G241DCUT"))
      (libsource (lib "eagle-import") (part "SN74LVC2G241DCU"))
    )
    (comp (ref "U23")
      (value "SN74LVC1G14DCK")
      (footprint "eagle-import:DCK_R-PDSO-G5")
      (fields
        (field (name "DISP") "SN74LVC1G14")
        (field (name "MF") "TI")
        (field (name "MPN") "SN74LVC1G14DCKR")
      )
      (libsource (lib "eagle-import") (part "SN741G14DCKLVC"))
    )
    (comp (ref "U25")
      (value "SN74AUP1T87")
      (footprint "eagle-import:DCK_R-PDSO-G5")
      (fields
        (field (name "DISP") "SN74AUP1T87")
        (field (name "MF") "TI")
        (field (name "MPN") "SN74AUP1T87DCKR")
      )
      (libsource (lib "eagle-import") (part "SN74AUP1T87"))
    )
  )
  (nets
    (net (code "1") (name "3V3") (class "Default")
      (node (ref "C1") (pin "1") (pinfunction "1_1") (pintype "passive"))
      (node (ref "C10") (pin "1") (pinfunction "1_1") (pintype "passive"))
      (node (ref "C12") (pin "1") (pinfunction "1_1") (pintype "passive"))
      (node (ref "C14") (pin "1") (pinfunction "1_1") (pintype "passive"))
      (node (ref "C16") (pin "1") (pinfunction "1_1") (pintype "passive"))
      (node (ref "C3") (pin "1") (pinfunction "1_1") (pintype "passive"))
      (node (ref "C4") (pin "1") (pinfunction "1_1") (pintype "passive"))
      (node (ref "C5") (pin "1") (pinfunction "1_1") (pintype "passive"))
      (node (ref "J2") (pin "2") (pinfunction "3V3_2") (pintype "passive"))
      (node (ref "L1") (pin "P$1") (pinfunction "1_P$1") (pintype "passive"))
      (node (ref "L2") (pin "1") (pinfunction "1_1") (pintype "passive"))
      (node (ref "R12") (pin "2") (pinfunction "2_2") (pintype "passive"))
      (node (ref "R13") (pin "2") (pinfunction "2_2") (pintype "passive"))
      (node (ref "R26") (pin "2") (pinfunction "2_2") (pintype "passive"))
      (node (ref "R27") (pin "2") (pinfunction "2_2") (pintype "passive"))
      (node (ref "U1") (pin "13") (pinfunction "A6_13") (pintype "input"))
      (node (ref "U1") (pin "14") (pinfunction "VCC_14") (pintype "power_in"))
      (node (ref "U10") (pin "1") (pinfunction "VA_1") (pintype "power_in"))
      (node (ref "U10") (pin "5") (pinfunction "EN_5") (pintype "input"))
      (node (ref "U11") (pin "16") (pinfunction "VCC_16") (pintype "power_in"))
      (node (ref "U12") (pin "5") (pinfunction "VCC_5") (pintype "power_in"))
      (node (ref "U14") (pin "18") (pinfunction "A0_18") (pintype "input"))
      (node (ref "U14") (pin "21") (pinfunction "VDD_21") (pintype "power_in"))
      (node (ref "U14") (pin "24") (pinfunction "A2_24") (pintype "input"))
      (node (ref "U15") (pin "8") (pinfunction "VCC_8") (pintype "power_in"))
      (node (ref "U16") (pin "5") (pinfunction "VDD_5") (pintype "passive"))
      (node (ref "U2") (pin "16") (pinfunction "VCC_16") (pintype "power_in"))
      (node (ref "U21") (pin "5") (pinfunction "VCC_5") (pintype "power_in"))
      (node (ref "U23") (pin "5") (pinfunction "VCC_5") (pintype "power_in"))
      (node (ref "U24") (pin "4") (pinfunction "VCC_4") (pintype "power_in"))
      (node (ref "U25") (pin "5") (pinfunction "VCC_5") (pintype "power_in"))
      (node (ref "U3") (pin "3") (pinfunction "VIN_3") (pintype "power_in"))
      (node (ref "U7") (pin "14") (pinfunction "VCC_14") (pintype "power_in"))
      (node (ref "U8") (pin "2") (pinfunction "EN_2") (pintype "bidirectional"))
      (node (ref "U8") (pin "6") (pinfunction "VDD_6") (pintype "bidirectional"))
      (node (ref "U8") (pin "7") (pinfunction "BOOT_7") (pintype "bidirectional"))
      (node (ref "U9") (pin "4") (pinfunction "~{SHDN}_4") (pintype "input"))
      (node (ref "U9") (pin "5") (pinfunction "VIN_5") (pintype "power_in"))
    )
    (net (code "2") (name "3V3_SENSE") (class "Default")
      (node (ref "C2") (pin "1") (pinfunction "1_1") (pintype "passive"))
      (node (ref "R11") (pin "2") (pinfunction "2_2") (pintype "passive"))
      (node (ref "U3") (pin "1") (pinfunction "VOUT_1") (pintype "power_in"))
      (node (ref "U4") (pin "4") (pinfunction "VDD_4") (pintype "power_in"))
      (node (ref "U5") (pin "4") (pinfunction "VDD_4") (pintype "power_in"))
    )
    (net (code "3") (name "5V") (class "Default")
      (node (ref "C11") (pin "1") (pinfunction "1_1") (pintype "passive"))
      (node (ref "C13") (pin "1") (pinfunction "1_1") (pintype "passive"))
      (node (ref "C15") (pin "1") (pinfunction "1_1") (pintype "passive"))
      (node (ref "C6") (pin "1") (pinfunction "1_1") (pintype "passive"))
      (node (ref "C8") (pin "1") (pinfunction "1_1") (pintype "passive"))
      (node (ref "D3") (pin "CAT") (pinfunction "C_CAT") (pintype "passive"))
      (node (ref "R22") (pin "2") (pinfunction "2_2") (pintype "passive"))
      (node (ref "U10") (pin "8") (pinfunction "VB_8") (pintype "power_in"))
      (node (ref "U13") (pin "1") (pinfunction "VDD_1") (pintype "power_in"))
      (node (ref "U17") (pin "5") (pinfunction "VCC_5") (pintype "power_in"))
      (node (ref "U18") (pin "5") (pinfunction "VCC_5") (pintype "power_in"))
      (node (ref "U19") (pin "5") (pinfunction "VCC_5") (pintype "power_in"))
      (node (ref "U20") (pin "5") (pinfunction "VCC_5") (pintype "power_in"))
      (node (ref "U22") (pin "8") (pinfunction "VCC_8") (pintype "power_in"))
    )
    (net (code "4") (name "12V") (class "Default")
      (node (ref "C7") (pin "1") (pinfunction "1_1") (pintype "passive"))
      (node (ref "C9") (pin "+") (pinfunction "+_+") (pintype "passive"))
      (node (ref "D2") (pin "C") (pinfunction "C_C") (pintype "passive"))
      (node (ref "Q5") (pin "2") (pinfunction "S_2") (pintype "bidirectional"))
      (node (ref "Q6") (pin "2") (pinfunction "S_2") (pintype "bidirectional"))
      (node (ref "Q7") (pin "2") (pinfunction "S_2") (pintype "bidirectional"))
      (node (ref "Q8") (pin "2") (pinfunction "S_2") (pintype "bidirectional"))
      (node (ref "R1") (pin "2") (pinfunction "2_2") (pintype "passive"))
      (node (ref "R10") (pin "2") (pinfunction "2_2") (pintype "passive"))
      (node (ref "R2") (pin "2") (pinfunction "2_2") (pintype "passive"))
      (node (ref "R24") (pin "2") (pinfunction "2_2") (pintype "passive"))
      (node (ref "R3") (pin "2") (pinfunction "2_2") (pintype "passive"))
      (node (ref "R4") (pin "2") (pinfunction "2_2") (pintype "passive"))
      (node (ref "U6") (pin "4") (pinfunction "VIN_4") (pintype "bidirectional"))
    )
    (net (code "5") (name "DATA") (class "Default")
      (node (ref "C22") (pin "1") (pinfunction "1_1") (pintype "passive"))
      (node (ref "R39") (pin "2") (pinfunction "2_2") (pintype "passive"))
      (node (ref "R41") (pin "1") (pinfunction "1_1") (pintype "passive"))
      (node (ref "TP4") (pin "1") (pinfunction "P$1_1") (pintype "bidirectional"))
      (node (ref "U17") (pin "1") (pinfunction "B2_1") (pintype "bidirectional"))
      (node (ref "U18") (pin "1") (pinfunction "B2_1") (pintype "bidirectional"))
      (node (ref "U19") (pin "1") (pinfunction "B2_1") (pintype "bidirectional"))
      (node (ref "U20") (pin "3") (pinfunction "B1_3") (pintype "bidirectional"))
    )
    (net (code "6") (name "DATA_EN1") (class "Default")
      (node (ref "U14") (pin "5") (pinfunction "P0_4_5") (pintype "bidirectional"))
      (node (ref "U17") (pin "6") (pinfunction "S_6") (pintype "input"))
    )
    (net (code "7") (name "DATA_EN2") (class "Default")
      (node (ref "U14") (pin "6") (pinfunction "P0_5_6") (pintype "bidirectional"))
      (node (ref "U18") (pin "6") (pinfunction "S_6") (pintype "input"))
    )
    (net (code "8") (name "DATA_EN3") (class "Default")
      (node (ref "U14") (pin "7") (pinfunction "P0_6_7") (pintype "bidirectional"))
      (node (ref "U19") (pin "6") (pinfunction "S_6") (pintype "input"))
    )
    (net (code "9") (name "DATA_EN4") (class "Default")
      (node (ref "U1") (pin "11") (pinfunction "A5_11") (pintype "input"))
      (node (ref "U14") (pin "8") (pinfunction "P0_7_8") (pintype "bidirectional"))
      (node (ref "U6") (pin "5") (pinfunction "EN_5") (pintype "bidirectional"))
    )
    (net (code "10") (name "DATA_OUT1") (class "Default")
      (node (ref "D4") (pin "2") (pinfunction "C_2") (pintype "passive"))
      (node (ref "J3") (pin "4") (pinfunction "DATA_4") (pintype "passive"))
      (node (ref "R40") (pin "1") (pinfunction "1_1") (pintype "passive"))
    )
    (net (code "11") (name "DATA_OUT2") (class "Default")
      (node (ref "D5") (pin "2") (pinfunction "C_2") (pintype "passive"))
      (node (ref "J4") (pin "4") (pinfunction "DATA_4") (pintype "passive"))
      (node (ref "R42") (pin "1") (pinfunction "1_1") (pintype "passive"))
    )
    (net (code "12") (name "DATA_OUT3") (class "Default")
      (node (ref "D6") (pin "2") (pinfunction "C_2") (pintype "passive"))
      (node (ref "J5") (pin "4") (pinfunction "DATA_4") (pintype "passive"))
      (node (ref "R43") (pin "1") (pinfunction "1_1") (pintype "passive"))
    )
    (net (code "13") (name "DATA_OUT4") (class "Default")
      (node (ref "D7") (pin "2") (pinfunction "C_2") (pintype "passive"))
      (node (ref "J1") (pin "3") (pinfunction "3_3") (pintype "passive"))
      (node (ref "R44") (pin "1") (pinfunction "1_1") (pintype "passive"))
    )
    (net (code "14") (name "DATA_OUT_PROTEC1") (class "Default")
      (node (ref "D8") (pin "C") (pinfunction "C_C") (pintype "passive"))
      (node (ref "R40") (pin "2") (pinfunction "2_2") (pintype "passive"))
      (node (ref "U17") (pin "4") (pinfunction "A_4") (pintype "bidirectional"))
    )
    (net (code "15") (name "DATA_OUT_PROTEC2") (class "Default")
      (node (ref "D9") (pin "C") (pinfunction "C_C") (pintype "passive"))
      (node (ref "R42") (pin "2") (pinfunction "2_2") (pintype "passive"))
      (node (ref "U18") (pin "4") (pinfunction "A_4") (pintype "bidirectional"))
    )
    (net (code "16") (name "DATA_OUT_PROTEC3") (class "Default")
      (node (ref "D10") (pin "C") (pinfunction "C_C") (pintype "passive"))
      (node (ref "R43") (pin "2") (pinfunction "2_2") (pintype "passive"))
      (node (ref "U19") (pin "4") (pinfunction "A_4") (pintype "bidirectional"))
    )
    (net (code "17") (name "DATA_OUT_PROTEC4") (class "Default")
      (node (ref "D11") (pin "C") (pinfunction "C_C") (pintype "passive"))
      (node (ref "R44") (pin "2") (pinfunction "2_2") (pintype "passive"))
      (node (ref "U20") (pin "4") (pinfunction "A_4") (pintype "bidirectional"))
    )
    (net (code "18") (name "DATA_PROTEC") (class "Default")
      (node (ref "R41") (pin "2") (pinfunction "2_2") (pintype "passive"))
      (node (ref "U22") (pin "2") (pinfunction "1A_2") (pintype "input"))
      (node (ref "U22") (pin "3") (pinfunction "2Y_3") (pintype "output"))
    )
    (net (code "19") (name "DATA_SENSE4") (class "Default")
      (node (ref "U13") (pin "3") (pinfunction "VIN_3") (pintype "input"))
      (node (ref "U20") (pin "1") (pinfunction "B2_1") (pintype "bidirectional"))
    )
    (net (code "20") (name "DIR") (class "Default")
      (node (ref "TP5") (pin "1") (pinfunction "P$1_1") (pintype "bidirectional"))
      (node (ref "U14") (pin "17") (pinfunction "P1_7_17") (pintype "bidirectional"))
      (node (ref "U22") (pin "1") (pinfunction "1~{OE}_1") (pintype "input"))
      (node (ref "U25") (pin "1") (pinfunction "A_1") (pintype "input"))
    )
    (net (code "21") (name "DIR_BYPASS") (class "Default")
      (node (ref "U22") (pin "7") (pinfunction "2OE_7") (pintype "input"))
      (node (ref "U25") (pin "4") (pinfunction "Y_4") (pintype "output"))
    )
    (net (code "22") (name "EN1") (class "Default")
      (node (ref "U14") (pin "1") (pinfunction "P0_0_1") (pintype "bidirectional"))
      (node (ref "U2") (pin "6") (pinfunction "R2_6") (pintype "input"))
      (node (ref "U7") (pin "12") (pinfunction "A4_12") (pintype "input"))
    )
    (net (code "23") (name "EN2") (class "Default")
      (node (ref "U14") (pin "2") (pinfunction "P0_1_2") (pintype "bidirectional"))
      (node (ref "U2") (pin "4") (pinfunction "R1_4") (pintype "input"))
      (node (ref "U7") (pin "1") (pinfunction "A1_1") (pintype "input"))
    )
    (net (code "24") (name "EN3") (class "Default")
      (node (ref "U14") (pin "3") (pinfunction "P0_2_3") (pintype "bidirectional"))
      (node (ref "U2") (pin "12") (pinfunction "R3_12") (pintype "input"))
      (node (ref "U7") (pin "9") (pinfunction "A3_9") (pintype "input"))
    )
    (net (code "25") (name "EN4") (class "Default")
      (node (ref "U14") (pin "4") (pinfunction "P0_3_4") (pintype "bidirectional"))
      (node (ref "U2") (pin "14") (pinfunction "R4_14") (pintype "input"))
      (node (ref "U7") (pin "4") (pinfunction "A2_4") (pintype "input"))
    )
    (net (code "26") (name "FAULT1") (class "Default")
      (node (ref "R34") (pin "2") (pinfunction "2_2") (pintype "passive"))
      (node (ref "U1") (pin "9") (pinfunction "A4_9") (pintype "input"))
      (node (ref "U2") (pin "9") (pinfunction "Q2_9") (pintype "output"))
    )
    (net (code "27") (name "FAULT1_SENSE") (class "Default")
      (node (ref "R34") (pin "1") (pinfunction "1_1") (pintype "passive"))
      (node (ref "U14") (pin "10") (pinfunction "P1_0_10") (pintype "bidirectional"))
    )
    (net (code "28") (name "FAULT2") (class "Default")
      (node (ref "R33") (pin "2") (pinfunction "2_2") (pintype "passive"))
      (node (ref "U1") (pin "3") (pinfunction "A2_3") (pintype "input"))
      (node (ref "U2") (pin "13") (pinfunction "Q1_13") (pintype "output"))
    )
    (net (code "29") (name "FAULT2_SENSE") (class "Default")
      (node (ref "R33") (pin "1") (pinfunction "1_1") (pintype "passive"))
      (node (ref "U14") (pin "11") (pinfunction "P1_1_11") (pintype "bidirectional"))
    )
    (net (code "30") (name "FAULT3") (class "Default")
      (node (ref "R32") (pin "2") (pinfunction "2_2") (pintype "passive"))
      (node (ref "U1") (pin "5") (pinfunction "A3_5") (pintype "input"))
      (node (ref "U2") (pin "10") (pinfunction "Q3_10") (pintype "output"))
    )
    (net (code "31") (name "FAULT3_SENSE") (class "Default")
      (node (ref "R32") (pin "1") (pinfunction "1_1") (pintype "passive"))
      (node (ref "U14") (pin "12") (pinfunction "P1_2_12") (pintype "bidirectional"))
    )
    (net (code "32") (name "FAULT4") (class "Default")
      (node (ref "R31") (pin "2") (pinfunction "2_2") (pintype "passive"))
      (node (ref "U1") (pin "1") (pinfunction "A1_1") (pintype "input"))
      (node (ref "U2") (pin "1") (pinfunction "Q4_1") (pintype "output"))
    )
    (net (code "33") (name "FAULT4_SENSE") (class "Default")
      (node (ref "R31") (pin "1") (pinfunction "1_1") (pintype "passive"))
      (node (ref "U14") (pin "13") (pinfunction "P1_3_13") (pintype "bidirectional"))
    )
    (net (code "34") (name "FOUT") (class "Default")
      (node (ref "U14") (pin "16") (pinfunction "P1_6_16") (pintype "bidirectional"))
      (node (ref "U21") (pin "1") (pinfunction "A_1") (pintype "input"))
    )
    (net (code "35") (name "GND") (class "Default")
      (node (ref "C1") (pin "2") (pinfunction "2_2") (pintype "passive"))
      (node (ref "C10") (pin "2") (pinfunction "2_2") (pintype "passive"))
      (node (ref "C11") (pin "2") (pinfunction "2_2") (pintype "passive"))
      (node (ref "C12") (pin "2") (pinfunction "2_2") (pintype "passive"))
      (node (ref "C13") (pin "2") (pinfunction "2_2") (pintype "passive"))
      (node (ref "C14") (pin "2") (pinfunction "2_2") (pintype "passive"))
      (node (ref "C15") (pin "2") (pinfunction "2_2") (pintype "passive"))
      (node (ref "C16") (pin "2") (pinfunction "2_2") (pintype "passive"))
      (node (ref "C17") (pin "2") (pinfunction "2_2") (pintype "passive"))
      (node (ref "C18") (pin "2") (pinfunction "2_2") (pintype "passive"))
      (node (ref "C19") (pin "2") (pinfunction "2_2") (pintype "passive"))
      (node (ref "C2") (pin "2") (pinfunction "2_2") (pintype "passive"))
      (node (ref "C20") (pin "2") (pinfunction "2_2") (pintype "passive"))
      (node (ref "C22") (pin "2") (pinfunction "2_2") (pintype "passive"))
      (node (ref "C3") (pin "2") (pinfunction "2_2") (pintype "passive"))
      (node (ref "C5") (pin "2") (pinfunction "2_2") (pintype "passive"))
      (node (ref "C8") (pin "2") (pinfunction "2_2") (pintype "passive"))
      (node (ref "C9") (pin "-") (pinfunction "-_-") (pintype "passive"))
      (node (ref "D1") (pin "2") (pinfunction "A_2") (pintype "power_in"))
      (node (ref "D10") (pin "A") (pinfunction "A_A") (pintype "passive"))
      (node (ref "D11") (pin "A") (pinfunction "A_A") (pintype "passive"))
      (node (ref "D4") (pin "1") (pinfunction "A_1") (pintype "passive"))
      (node (ref "D5") (pin "1") (pinfunction "A_1") (pintype "passive"))
      (node (ref "D6") (pin "1") (pinfunction "A_1") (pintype "passive"))
      (node (ref "D7") (pin "1") (pinfunction "A_1") (pintype "passive"))
      (node (ref "D8") (pin "A") (pinfunction "A_A") (pintype "passive"))
      (node (ref "D9") (pin "A") (pinfunction "A_A") (pintype "passive"))
      (node (ref "J1") (pin "1") (pinfunction "1_1") (pintype "passive"))
      (node (ref "J1") (pin "6") (pinfunction "6_6") (pintype "passive"))
      (node (ref "J2") (pin "1") (pinfunction "GND_1") (pintype "passive"))
      (node (ref "J3") (pin "3") (pinfunction "GND_3") (pintype "passive"))
      (node (ref "J4") (pin "3") (pinfunction "GND_3") (pintype "passive"))
      (node (ref "J5") (pin "3") (pinfunction "GND_3") (pintype "passive"))
      (node (ref "Q1") (pin "2") (pinfunction "S_2") (pintype "bidirectional"))
      (node (ref "Q2") (pin "2") (pinfunction "S_2") (pintype "bidirectional"))
      (node (ref "Q3") (pin "2") (pinfunction "S_2") (pintype "bidirectional"))
      (node (ref "Q4") (pin "2") (pinfunction "S_2") (pintype "bidirectional"))
      (node (ref "R18") (pin "1") (pinfunction "1_1") (pintype "passive"))
      (node (ref "R19") (pin "1") (pinfunction "1_1") (pintype "passive"))
      (node (ref "R20") (pin "1") (pinfunction "1_1") (pintype "passive"))
      (node (ref "R21") (pin "1") (pinfunction "1_1") (pintype "passive"))
      (node (ref "R23") (pin "1") (pinfunction "1_1") (pintype "passive"))
      (node (ref "R25") (pin "1") (pinfunction "1_1") (pintype "passive"))
      (node (ref "R39") (pin "1") (pinfunction "1_1") (pintype "passive"))
      (node (ref "R9") (pin "1") (pinfunction "1_1") (pintype "passive"))
      (node (ref "S1") (pin "1") (pinfunction "O_1") (pintype "passive"))
      (node (ref "TP1") (pin "1") (pinfunction "P$1_1") (pintype "bidirectional"))
      (node (ref "U1") (pin "7") (pinfunction "GND_7") (pintype "power_in"))
      (node (ref "U10") (pin "4") (pinfunction "GND_4") (pintype "power_in"))
      (node (ref "U11") (pin "8") (pinfunction "GND_8") (pintype "power_in"))
      (node (ref "U11") (pin "EP") (pinfunction "GND_EP") (pintype "power_in"))
      (node (ref "U12") (pin "2") (pinfunction "GND_2") (pintype "power_in"))
      (node (ref "U13") (pin "2") (pinfunction "VSS_2") (pintype "power_in"))
      (node (ref "U14") (pin "23") (pinfunction "A1_23") (pintype "input"))
      (node (ref "U14") (pin "9") (pinfunction "VSS_9") (pintype "power_in"))
      (node (ref "U14") (pin "EP") (pinfunction "VSS_EP") (pintype "power_in"))
      (node (ref "U15") (pin "4") (pinfunction "GND_4") (pintype "power_in"))
      (node (ref "U15") (pin "EP") (pinfunction "GND_EP") (pintype "power_in"))
      (node (ref "U16") (pin "2") (pinfunction "VSS_2") (pintype "passive"))
      (node (ref "U16") (pin "6") (pinfunction "VIN-_6") (pintype "input"))
      (node (ref "U17") (pin "2") (pinfunction "GND_2") (pintype "power_in"))
      (node (ref "U18") (pin "2") (pinfunction "GND_2") (pintype "power_in"))
      (node (ref "U19") (pin "2") (pinfunction "GND_2") (pintype "power_in"))
      (node (ref "U2") (pin "8") (pinfunction "GND_8") (pintype "power_in"))
      (node (ref "U20") (pin "2") (pinfunction "GND_2") (pintype "power_in"))
      (node (ref "U21") (pin "3") (pinfunction "GND_3") (pintype "power_in"))
      (node (ref "U22") (pin "4") (pinfunction "GND_4") (pintype "power_in"))
      (node (ref "U23") (pin "3") (pinfunction "GND_3") (pintype "power_in"))
      (node (ref "U24") (pin "2") (pinfunction "GND_2") (pintype "power_in"))
      (node (ref "U24") (pin "5") (pinfunction "WP_5") (pintype "input"))
      (node (ref "U25") (pin "3") (pinfunction "GND_3") (pintype "power_in"))
      (node (ref "U3") (pin "2") (pinfunction "GND_2") (pintype "power_in"))
      (node (ref "U3") (pin "EP") (pinfunction "GND_EP") (pintype "power_in"))
      (node (ref "U4") (pin "11") (pinfunction "GND_11") (pintype "power_in"))
      (node (ref "U5") (pin "11") (pinfunction "GND_11") (pintype "power_in"))
      (node (ref "U6") (pin "1") (pinfunction "R2_1") (pintype "bidirectional"))
      (node (ref "U7") (pin "7") (pinfunction "GND_7") (pintype "power_in"))
      (node (ref "U8") (pin "1") (pinfunction "PGND_1") (pintype "bidirectional"))
      (node (ref "U8") (pin "5") (pinfunction "SGND_5") (pintype "bidirectional"))
      (node (ref "U9") (pin "2") (pinfunction "GND_2") (pintype "power_in"))
    )
    (net (code "36") (name "LATCH1") (class "Default")
      (node (ref "U2") (pin "7") (pinfunction "S2_7") (pintype "input"))
      (node (ref "U5") (pin "1") (pinfunction "OUTA_1") (pintype "output"))
    )
    (net (code "37") (name "LATCH2") (class "Default")
      (node (ref "U2") (pin "3") (pinfunction "S1_3") (pintype "input"))
      (node (ref "U5") (pin "7") (pinfunction "OUTB_7") (pintype "output"))
    )
    (net (code "38") (name "LATCH3") (class "Default")
      (node (ref "U2") (pin "11") (pinfunction "S3_11") (pintype "input"))
      (node (ref "U5") (pin "8") (pinfunction "OUTC_8") (pintype "output"))
    )
    (net (code "39") (name "LATCH4") (class "Default")
      (node (ref "U2") (pin "15") (pinfunction "S4_15") (pintype "input"))
      (node (ref "U5") (pin "14") (pinfunction "OUTD_14") (pintype "output"))
    )
    (net (code "40") (name "MOS_CTRL1") (class "Default")
      (node (ref "Q1") (pin "1") (pinfunction "G_1") (pintype "bidirectional"))
      (node (ref "U7") (pin "11") (pinfunction "Y4_11") (pintype "output"))
    )
    (net (code "41") (name "MOS_CTRL2") (class "Default")
      (node (ref "Q2") (pin "1") (pinfunction "G_1") (pintype "bidirectional"))
      (node (ref "U7") (pin "3") (pinfunction "Y1_3") (pintype "output"))
    )
    (net (code "42") (name "MOS_CTRL3") (class "Default")
      (node (ref "Q3") (pin "1") (pinfunction "G_1") (pintype "bidirectional"))
      (node (ref "U7") (pin "8") (pinfunction "Y3_8") (pintype "output"))
    )
    (net (code "43") (name "MOS_CTRL4") (class "Default")
      (node (ref "Q4") (pin "1") (pinfunction "G_1") (pintype "bidirectional"))
      (node (ref "U7") (pin "6") (pinfunction "Y2_6") (pintype "output"))
    )
    (net (code "44") (name "MUX_EN") (class "Default")
      (node (ref "U11") (pin "6") (pinfunction "~{E}_6") (pintype "input"))
      (node (ref "U15") (pin "5") (pinfunction "P3_5") (pintype "bidirectional"))
      (node (ref "U25") (pin "2") (pinfunction "B_2") (pintype "input"))
    )
    (net (code "45") (name "MUX_SEL0") (class "Default")
      (node (ref "U11") (pin "10") (pinfunction "S0_10") (pintype "input"))
      (node (ref "U15") (pin "1") (pinfunction "P0_1") (pintype "bidirectional"))
    )
    (net (code "46") (name "MUX_SEL1") (class "Default")
      (node (ref "U11") (pin "9") (pinfunction "S1_9") (pintype "input"))
      (node (ref "U15") (pin "2") (pinfunction "P1_2") (pintype "bidirectional"))
    )
    (net (code "47") (name "MUX_SEL2") (class "Default")
      (node (ref "U12") (pin "6") (pinfunction "S_6") (pintype "input"))
      (node (ref "U15") (pin "3") (pinfunction "P2_3") (pintype "bidirectional"))
    )
    (net (code "48") (name "Net-(D3-A)") (class "Default")
      (node (ref "D3") (pin "ANODE") (pinfunction "A_ANODE") (pintype "passive"))
      (node (ref "L2") (pin "2") (pinfunction "2_2") (pintype "passive"))
      (node (ref "U9") (pin "1") (pinfunction "SW_1") (pintype "power_in"))
    )
    (net (code "49") (name "Net-(L1-2)") (class "Default")
      (node (ref "C21") (pin "1") (pinfunction "1_1") (pintype "passive"))
      (node (ref "D2") (pin "A") (pinfunction "A_A") (pintype "passive"))
      (node (ref "L1") (pin "P$2") (pinfunction "2_P$2") (pintype "passive"))
      (node (ref "U8") (pin "8") (pinfunction "SW_8") (pintype "bidirectional"))
    )
    (net (code "50") (name "Net-(Q1-D)") (class "Default")
      (node (ref "Q1") (pin "3") (pinfunction "D_3") (pintype "bidirectional"))
      (node (ref "Q5") (pin "1") (pinfunction "G_1") (pintype "bidirectional"))
      (node (ref "R1") (pin "1") (pinfunction "1_1") (pintype "passive"))
    )
    (net (code "51") (name "Net-(Q2-D)") (class "Default")
      (node (ref "Q2") (pin "3") (pinfunction "D_3") (pintype "bidirectional"))
      (node (ref "Q6") (pin "1") (pinfunction "G_1") (pintype "bidirectional"))
      (node (ref "R2") (pin "1") (pinfunction "1_1") (pintype "passive"))
    )
    (net (code "52") (name "Net-(Q3-D)") (class "Default")
      (node (ref "Q3") (pin "3") (pinfunction "D_3") (pintype "bidirectional"))
      (node (ref "Q7") (pin "1") (pinfunction "G_1") (pintype "bidirectional"))
      (node (ref "R3") (pin "1") (pinfunction "1_1") (pintype "passive"))
    )
    (net (code "53") (name "Net-(Q4-D)") (class "Default")
      (node (ref "Q4") (pin "3") (pinfunction "D_3") (pintype "bidirectional"))
      (node (ref "Q8") (pin "1") (pinfunction "G_1") (pintype "bidirectional"))
      (node (ref "R4") (pin "1") (pinfunction "1_1") (pintype "passive"))
    )
    (net (code "54") (name "Net-(U6-R1,C1)") (class "Default")
      (node (ref "R10") (pin "1") (pinfunction "1_1") (pintype "passive"))
      (node (ref "U6") (pin "6") (pinfunction "R1,C1_6") (pintype "bidirectional"))
    )
    (net (code "55") (name "Net-(U8-FB)") (class "Default")
      (node (ref "C7") (pin "2") (pinfunction "2_2") (pintype "passive"))
      (node (ref "R24") (pin "1") (pinfunction "1_1") (pintype "passive"))
      (node (ref "R25") (pin "2") (pinfunction "2_2") (pintype "passive"))
      (node (ref "U8") (pin "4") (pinfunction "FB_4") (pintype "bidirectional"))
    )
    (net (code "56") (name "Net-(U8-FREQ)") (class "Default")
      (node (ref "C21") (pin "2") (pinfunction "2_2") (pintype "passive"))
      (node (ref "C4") (pin "2") (pinfunction "2_2") (pintype "passive"))
      (node (ref "R13") (pin "1") (pinfunction "1_1") (pintype "passive"))
      (node (ref "U8") (pin "3") (pinfunction "FREQ_3") (pintype "bidirectional"))
    )
    (net (code "57") (name "Net-(U9-FB)") (class "Default")
      (node (ref "C6") (pin "2") (pinfunction "2_2") (pintype "passive"))
      (node (ref "R22") (pin "1") (pinfunction "1_1") (pintype "passive"))
      (node (ref "R23") (pin "2") (pinfunction "2_2") (pintype "passive"))
      (node (ref "U9") (pin "3") (pinfunction "FB_3") (pintype "input"))
    )
    (net (code "58") (name "Net-(U11-1Z)") (class "Default")
      (node (ref "U11") (pin "13") (pinfunction "1Z_13") (pintype "output"))
      (node (ref "U12") (pin "1") (pinfunction "B2_1") (pintype "bidirectional"))
    )
    (net (code "59") (name "Net-(U11-2Z)") (class "Default")
      (node (ref "U11") (pin "3") (pinfunction "2Z_3") (pintype "output"))
      (node (ref "U12") (pin "3") (pinfunction "B1_3") (pintype "bidirectional"))
    )
    (net (code "60") (name "Net-(U21-Y)") (class "Default")
      (node (ref "U21") (pin "4") (pinfunction "Y_4") (pintype "output"))
      (node (ref "U22") (pin "5") (pinfunction "2A_5") (pintype "input"))
    )
    (net (code "61") (name "POS_DETECT") (class "Default")
      (node (ref "R12") (pin "1") (pinfunction "1_1") (pintype "passive"))
      (node (ref "S1") (pin "2") (pinfunction "P_2") (pintype "passive"))
      (node (ref "U14") (pin "14") (pinfunction "P1_4_14") (pintype "bidirectional"))
    )
    (net (code "62") (name "RX") (class "Default")
      (node (ref "J2") (pin "6") (pinfunction "RX_6") (pintype "passive"))
      (node (ref "TP3") (pin "1") (pinfunction "P$1_1") (pintype "bidirectional"))
      (node (ref "U23") (pin "4") (pinfunction "Y_4") (pintype "output"))
    )
    (net (code "63") (name "SCL") (class "Default")
      (node (ref "J2") (pin "4") (pinfunction "SCL_4") (pintype "passive"))
      (node (ref "R27") (pin "1") (pinfunction "1_1") (pintype "passive"))
      (node (ref "TP7") (pin "1") (pinfunction "P$1_1") (pintype "bidirectional"))
      (node (ref "U10") (pin "3") (pinfunction "A2_3") (pintype "bidirectional"))
      (node (ref "U14") (pin "19") (pinfunction "SCL_19") (pintype "input"))
      (node (ref "U15") (pin "6") (pinfunction "SCL_6") (pintype "input"))
      (node (ref "U16") (pin "3") (pinfunction "SCL_3") (pintype "bidirectional"))
      (node (ref "U24") (pin "1") (pinfunction "SCL_1") (pintype "input"))
    )
    (net (code "64") (name "SCL_HV") (class "Default")
      (node (ref "U10") (pin "6") (pinfunction "B2_6") (pintype "bidirectional"))
      (node (ref "U13") (pin "5") (pinfunction "SCL_5") (pintype "bidirectional"))
    )
    (net (code "65") (name "SDA") (class "Default")
      (node (ref "J2") (pin "3") (pinfunction "SDA_3") (pintype "passive"))
      (node (ref "R26") (pin "1") (pinfunction "1_1") (pintype "passive"))
      (node (ref "TP6") (pin "1") (pinfunction "P$1_1") (pintype "bidirectional"))
      (node (ref "U10") (pin "2") (pinfunction "A1_2") (pintype "bidirectional"))
      (node (ref "U14") (pin "20") (pinfunction "SDA_20") (pintype "bidirectional"))
      (node (ref "U15") (pin "7") (pinfunction "SDA_7") (pintype "bidirectional"))
      (node (ref "U16") (pin "4") (pinfunction "SDA_4") (pintype "bidirectional"))
      (node (ref "U24") (pin "3") (pinfunction "SDA_3") (pintype "bidirectional"))
    )
    (net (code "66") (name "SDA_HV") (class "Default")
      (node (ref "U10") (pin "7") (pinfunction "B1_7") (pintype "bidirectional"))
      (node (ref "U13") (pin "4") (pinfunction "SDA_4") (pintype "bidirectional"))
    )
    (net (code "67") (name "SENSE1") (class "Default")
      (node (ref "R35") (pin "1") (pinfunction "1_1") (pintype "passive"))
      (node (ref "U11") (pin "12") (pinfunction "1Y0_12") (pintype "input"))
      (node (ref "U4") (pin "7") (pinfunction "OUT2_7") (pintype "output"))
    )
    (net (code "68") (name "SENSE1+") (class "Default")
      (node (ref "Q5") (pin "3") (pinfunction "D_3") (pintype "bidirectional"))
      (node (ref "R5") (pin "1") (pinfunction "1_1") (pintype "passive"))
      (node (ref "U4") (pin "5") (pinfunction "IN2+_5") (pintype "input"))
    )
    (net (code "69") (name "SENSE1_FILT") (class "Default")
      (node (ref "C17") (pin "1") (pinfunction "1_1") (pintype "passive"))
      (node (ref "R35") (pin "2") (pinfunction "2_2") (pintype "passive"))
      (node (ref "U5") (pin "2") (pinfunction "INA-_2") (pintype "input"))
    )
    (net (code "70") (name "SENSE2") (class "Default")
      (node (ref "R36") (pin "1") (pinfunction "1_1") (pintype "passive"))
      (node (ref "U11") (pin "14") (pinfunction "1Y1_14") (pintype "input"))
      (node (ref "U4") (pin "1") (pinfunction "OUT1_1") (pintype "output"))
    )
    (net (code "71") (name "SENSE2+") (class "Default")
      (node (ref "Q6") (pin "3") (pinfunction "D_3") (pintype "bidirectional"))
      (node (ref "R6") (pin "1") (pinfunction "1_1") (pintype "passive"))
      (node (ref "U4") (pin "3") (pinfunction "IN1+_3") (pintype "input"))
    )
    (net (code "72") (name "SENSE2_FILT") (class "Default")
      (node (ref "C18") (pin "1") (pinfunction "1_1") (pintype "passive"))
      (node (ref "R36") (pin "2") (pinfunction "2_2") (pintype "passive"))
      (node (ref "U5") (pin "6") (pinfunction "INB-_6") (pintype "input"))
    )
    (net (code "73") (name "SENSE3") (class "Default")
      (node (ref "R37") (pin "1") (pinfunction "1_1") (pintype "passive"))
      (node (ref "U11") (pin "15") (pinfunction "1Y2_15") (pintype "input"))
      (node (ref "U4") (pin "14") (pinfunction "OUT4_14") (pintype "output"))
    )
    (net (code "74") (name "SENSE3+") (class "Default")
      (node (ref "Q7") (pin "3") (pinfunction "D_3") (pintype "bidirectional"))
      (node (ref "R7") (pin "1") (pinfunction "1_1") (pintype "passive"))
      (node (ref "U4") (pin "12") (pinfunction "IN4+_12") (pintype "input"))
    )
    (net (code "75") (name "SENSE3_FILT") (class "Default")
      (node (ref "C19") (pin "1") (pinfunction "1_1") (pintype "passive"))
      (node (ref "R37") (pin "2") (pinfunction "2_2") (pintype "passive"))
      (node (ref "U5") (pin "9") (pinfunction "INC-_9") (pintype "input"))
    )
    (net (code "76") (name "SENSE4") (class "Default")
      (node (ref "R38") (pin "1") (pinfunction "1_1") (pintype "passive"))
      (node (ref "U11") (pin "11") (pinfunction "1Y3_11") (pintype "input"))
      (node (ref "U4") (pin "8") (pinfunction "OUT3_8") (pintype "output"))
    )
    (net (code "77") (name "SENSE4+") (class "Default")
      (node (ref "Q8") (pin "3") (pinfunction "D_3") (pintype "bidirectional"))
      (node (ref "R8") (pin "1") (pinfunction "1_1") (pintype "passive"))
      (node (ref "U4") (pin "10") (pinfunction "IN3+_10") (pintype "input"))
    )
    (net (code "78") (name "SENSE4_FILT") (class "Default")
      (node (ref "C20") (pin "1") (pinfunction "1_1") (pintype "passive"))
      (node (ref "R38") (pin "2") (pinfunction "2_2") (pintype "passive"))
      (node (ref "U5") (pin "13") (pinfunction "IND-_13") (pintype "input"))
    )
    (net (code "79") (name "SENSE_EN") (class "Default")
      (node (ref "R9") (pin "2") (pinfunction "2_2") (pintype "passive"))
      (node (ref "U14") (pin "15") (pinfunction "P1_5_15") (pintype "bidirectional"))
      (node (ref "U2") (pin "5") (pinfunction "EN_5") (pintype "input"))
      (node (ref "U3") (pin "4") (pinfunction "EN_4") (pintype "input"))
    )
    (net (code "80") (name "SWITCHED_SENSE") (class "Default")
      (node (ref "U12") (pin "4") (pinfunction "A_4") (pintype "bidirectional"))
      (node (ref "U16") (pin "1") (pinfunction "VIN+_1") (pintype "input"))
    )
    (net (code "81") (name "TX") (class "Default")
      (node (ref "J2") (pin "5") (pinfunction "TX_5") (pintype "passive"))
      (node (ref "TP2") (pin "1") (pinfunction "P$1_1") (pintype "bidirectional"))
      (node (ref "U21") (pin "2") (pinfunction "B_2") (pintype "input"))
    )
    (net (code "82") (name "VHEATER") (class "Default")
      (node (ref "J1") (pin "5") (pinfunction "5_5") (pintype "passive"))
      (node (ref "U6") (pin "2") (pinfunction "VOUT_2") (pintype "bidirectional"))
      (node (ref "U6") (pin "3") (pinfunction "VOUT_3") (pintype "bidirectional"))
    )
    (net (code "83") (name "VPORT1_OUT") (class "Default")
      (node (ref "J3") (pin "1") (pinfunction "12V_1") (pintype "passive"))
      (node (ref "R14") (pin "1") (pinfunction "1_1") (pintype "passive"))
      (node (ref "R5") (pin "2") (pinfunction "2_2") (pintype "passive"))
      (node (ref "U4") (pin "6") (pinfunction "IN2-_6") (pintype "input"))
    )
    (net (code "84") (name "VPORT1_OUT_SENSE") (class "Default")
      (node (ref "R14") (pin "2") (pinfunction "2_2") (pintype "passive"))
      (node (ref "R18") (pin "2") (pinfunction "2_2") (pintype "passive"))
      (node (ref "U11") (pin "1") (pinfunction "2Y0_1") (pintype "input"))
    )
    (net (code "85") (name "VPORT2_OUT") (class "Default")
      (node (ref "J4") (pin "1") (pinfunction "12V_1") (pintype "passive"))
      (node (ref "R15") (pin "1") (pinfunction "1_1") (pintype "passive"))
      (node (ref "R6") (pin "2") (pinfunction "2_2") (pintype "passive"))
      (node (ref "U4") (pin "2") (pinfunction "IN1-_2") (pintype "input"))
    )
    (net (code "86") (name "VPORT2_OUT_SENSE") (class "Default")
      (node (ref "R15") (pin "2") (pinfunction "2_2") (pintype "passive"))
      (node (ref "R19") (pin "2") (pinfunction "2_2") (pintype "passive"))
      (node (ref "U11") (pin "5") (pinfunction "2Y1_5") (pintype "input"))
    )
    (net (code "87") (name "VPORT3_OUT") (class "Default")
      (node (ref "J5") (pin "1") (pinfunction "12V_1") (pintype "passive"))
      (node (ref "R16") (pin "1") (pinfunction "1_1") (pintype "passive"))
      (node (ref "R7") (pin "2") (pinfunction "2_2") (pintype "passive"))
      (node (ref "U4") (pin "13") (pinfunction "IN4-_13") (pintype "input"))
    )
    (net (code "88") (name "VPORT3_OUT_SENSE") (class "Default")
      (node (ref "R16") (pin "2") (pinfunction "2_2") (pintype "passive"))
      (node (ref "R20") (pin "2") (pinfunction "2_2") (pintype "passive"))
      (node (ref "U11") (pin "2") (pinfunction "2Y2_2") (pintype "input"))
    )
    (net (code "89") (name "VPORT4_OUT") (class "Default")
      (node (ref "J1") (pin "2") (pinfunction "2_2") (pintype "passive"))
      (node (ref "R17") (pin "1") (pinfunction "1_1") (pintype "passive"))
      (node (ref "R8") (pin "2") (pinfunction "2_2") (pintype "passive"))
      (node (ref "U4") (pin "9") (pinfunction "IN3-_9") (pintype "input"))
    )
    (net (code "90") (name "VPORT4_OUT_SENSE") (class "Default")
      (node (ref "R17") (pin "2") (pinfunction "2_2") (pintype "passive"))
      (node (ref "R21") (pin "2") (pinfunction "2_2") (pintype "passive"))
      (node (ref "U11") (pin "4") (pinfunction "2Y3_4") (pintype "input"))
    )
    (net (code "91") (name "VREF") (class "Default")
      (node (ref "D1") (pin "1") (pinfunction "C_1") (pintype "power_in"))
      (node (ref "R11") (pin "1") (pinfunction "1_1") (pintype "passive"))
      (node (ref "U5") (pin "10") (pinfunction "INC+_10") (pintype "input"))
      (node (ref "U5") (pin "12") (pinfunction "IND+_12") (pintype "input"))
      (node (ref "U5") (pin "3") (pinfunction "INA+_3") (pintype "input"))
      (node (ref "U5") (pin "5") (pinfunction "INB+_5") (pintype "input"))
    )
    (net (code "92") (name "unconnected-(J1-Pad4)") (class "Default")
      (node (ref "J1") (pin "4") (pinfunction "4_4") (pintype "passive"))
    )
    (net (code "93") (name "unconnected-(U1-Y6-Pad12)") (class "Default")
      (node (ref "U1") (pin "12") (pinfunction "Y6_12") (pintype "output"))
    )
    (net (code "94") (name "unconnected-(U14-~{INT}-Pad22)") (class "Default")
      (node (ref "U14") (pin "22") (pinfunction "~{INT}_22") (pintype "output"))
    )
    (net (code "95") (name "unconnected-(U17-B1-Pad3)") (class "Default")
      (node (ref "U17") (pin "3") (pinfunction "B1_3") (pintype "bidirectional"))
    )
    (net (code "96") (name "unconnected-(U18-B1-Pad3)") (class "Default")
      (node (ref "U18") (pin "3") (pinfunction "B1_3") (pintype "bidirectional"))
    )
    (net (code "97") (name "unconnected-(U19-B1-Pad3)") (class "Default")
      (node (ref "U19") (pin "3") (pinfunction "B1_3") (pintype "bidirectional"))
    )
    (net (code "98") (name "~{DATA_EN4}") (class "Default")
      (node (ref "U1") (pin "10") (pinfunction "Y5_10") (pintype "output"))
      (node (ref "U20") (pin "6") (pinfunction "S_6") (pintype "input"))
    )
    (net (code "99") (name "~{FAULT1}") (class "Default")
      (node (ref "U1") (pin "8") (pinfunction "Y4_8") (pintype "output"))
      (node (ref "U7") (pin "13") (pinfunction "B4_13") (pintype "input"))
    )
    (net (code "100") (name "~{FAULT2}") (class "Default")
      (node (ref "U1") (pin "4") (pinfunction "Y2_4") (pintype "output"))
      (node (ref "U7") (pin "2") (pinfunction "B1_2") (pintype "input"))
    )
    (net (code "101") (name "~{FAULT3}") (class "Default")
      (node (ref "U1") (pin "6") (pinfunction "Y3_6") (pintype "output"))
      (node (ref "U7") (pin "10") (pinfunction "B3_10") (pintype "input"))
    )
    (net (code "102") (name "~{FAULT4}") (class "Default")
      (node (ref "U1") (pin "2") (pinfunction "Y1_2") (pintype "output"))
      (node (ref "U7") (pin "5") (pinfunction "B2_5") (pintype "input"))
    )
    (net (code "103") (name "~{RX}") (class "Default")
      (node (ref "U22") (pin "6") (pinfunction "1Y_6") (pintype "output"))
      (node (ref "U23") (pin "2") (pinfunction "A_2") (pintype "input"))
    )
  )
)
